# LinuxBoard_v1_91.net
KiCad netlist of a schematic drawn in EAGLE
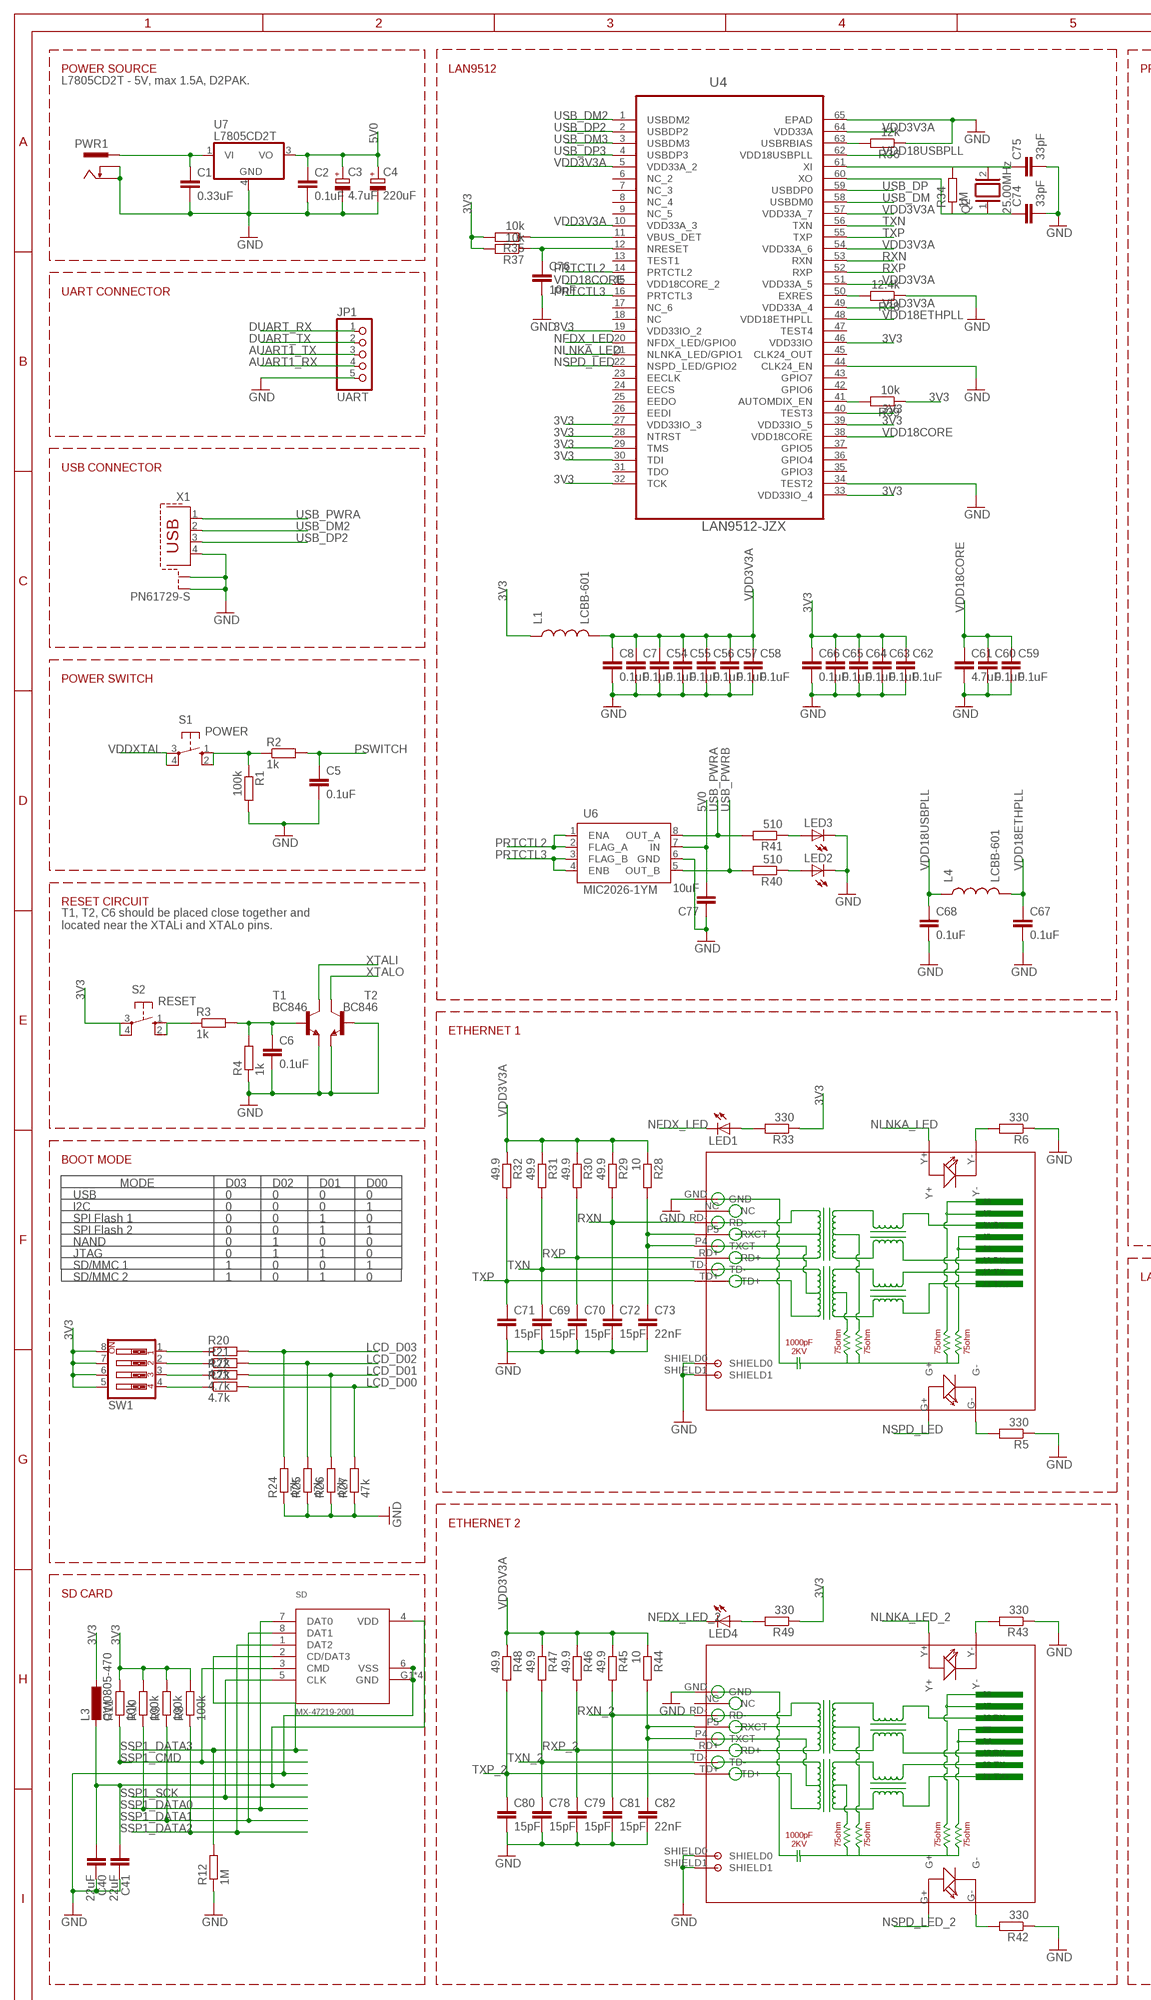
[diagram p0: schematic, sheet 1, part 1 of 2]
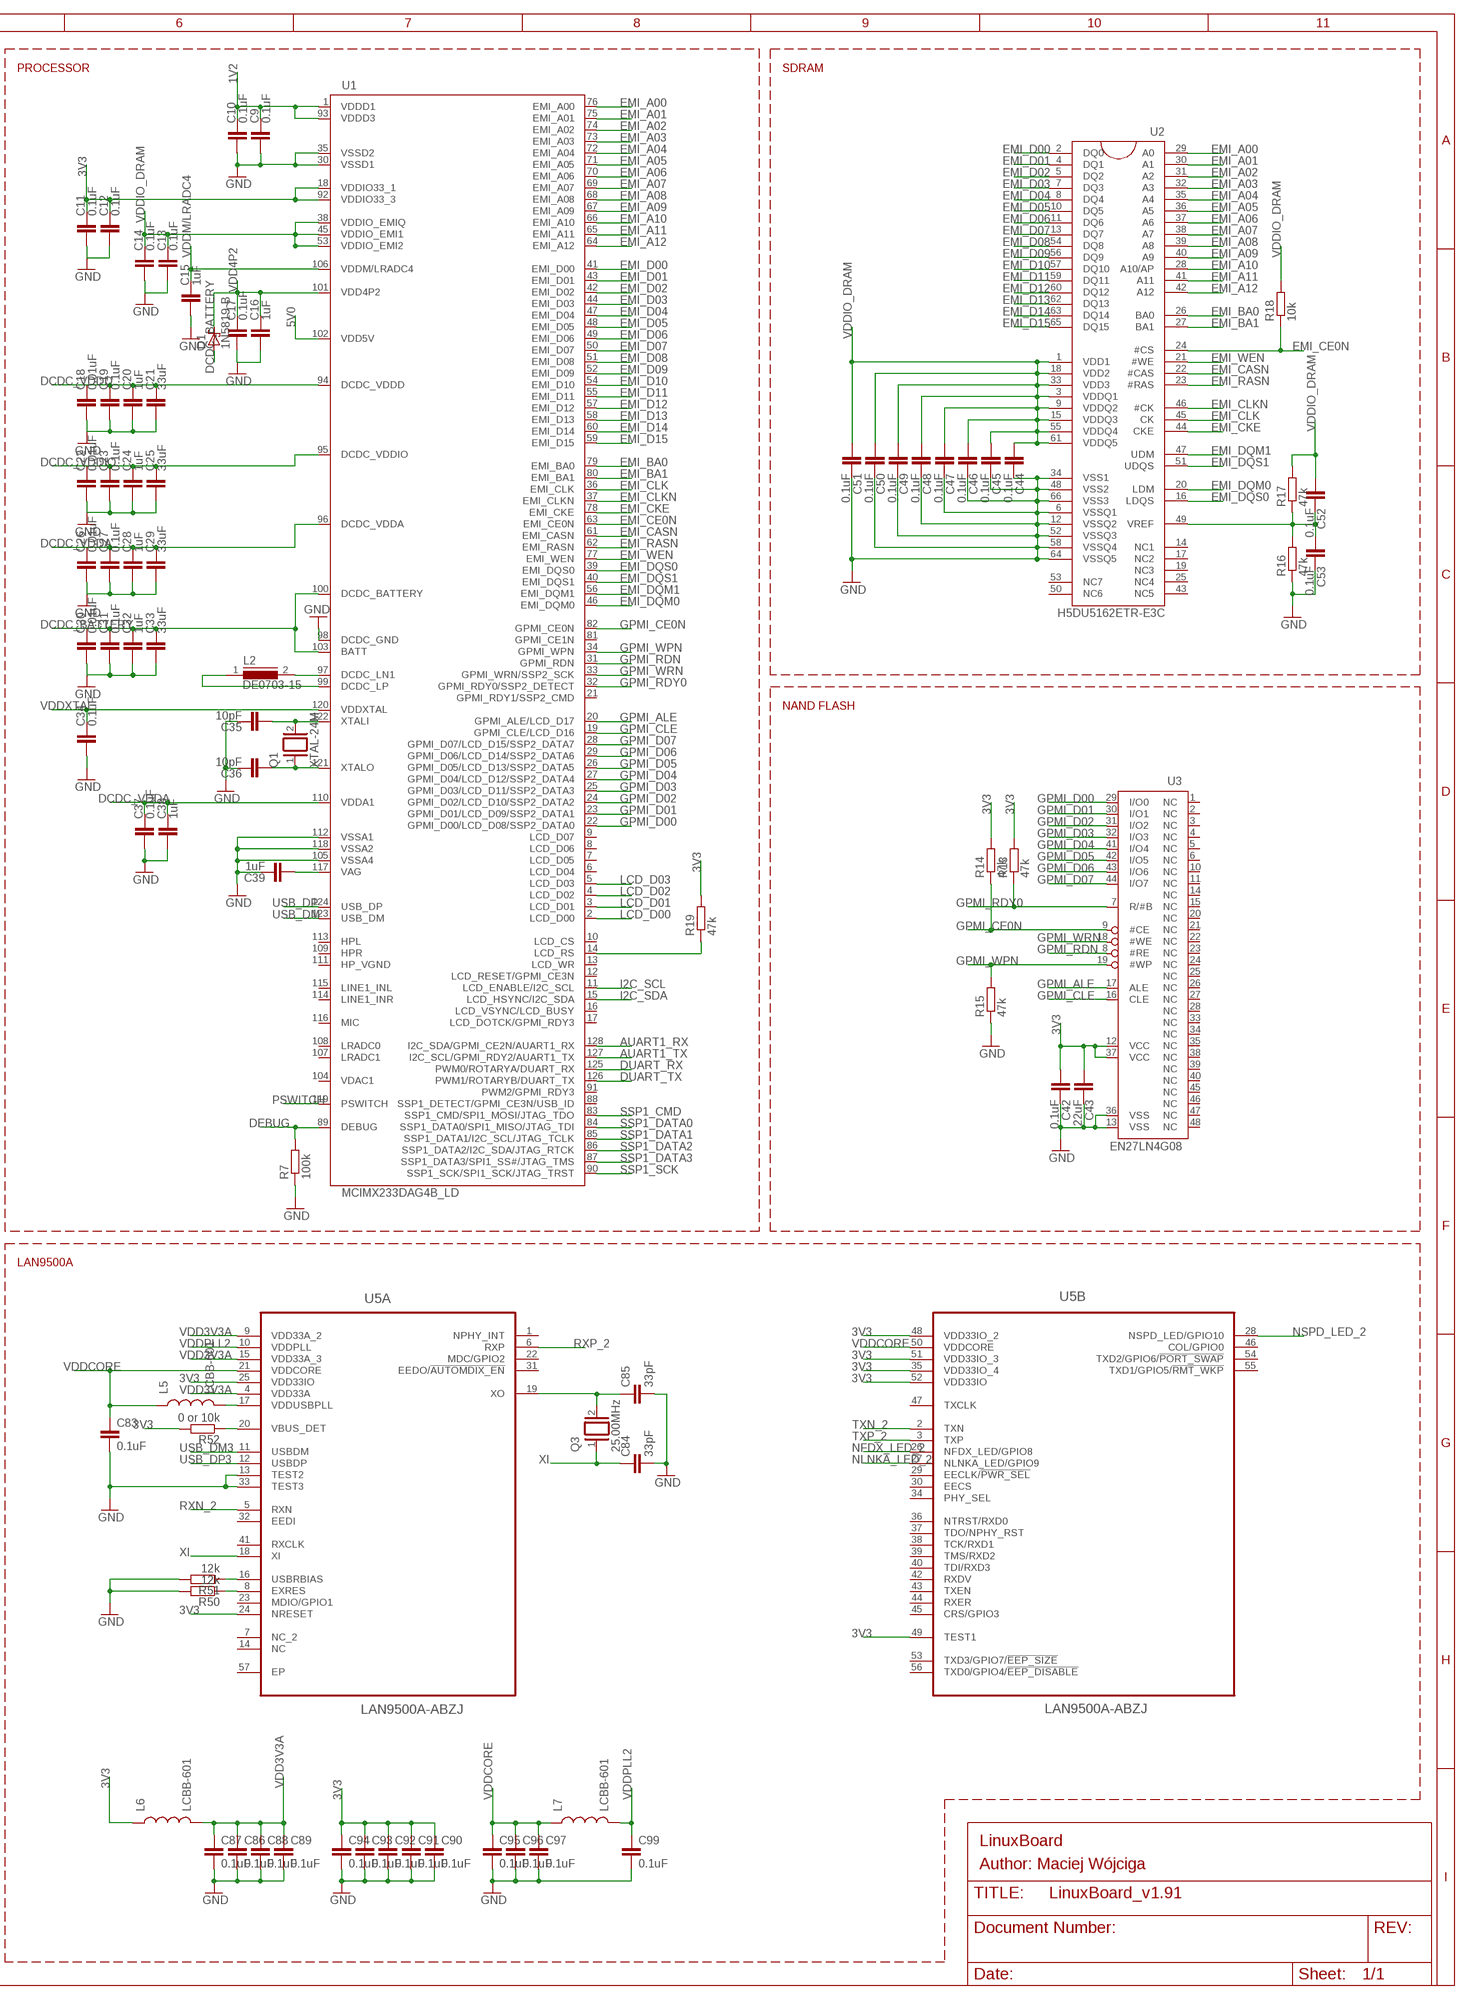
[diagram p1: schematic, sheet 1, part 2 of 2]

(export (version "E")
  (design (tool "Eeschema 10.0.6"))
  (components
    (comp (ref "C1")
      (value "0.33uF")
      (footprint "eagle-import:C0805")
      (libsource (lib "eagle-import") (part "C-EUC0805"))
    )
    (comp (ref "C2")
      (value "0.1uF")
      (footprint "eagle-import:C0805")
      (libsource (lib "eagle-import") (part "C-EUC0805"))
    )
    (comp (ref "C3")
      (value "4.7uF")
      (footprint "eagle-import:E2-5")
      (libsource (lib "eagle-import") (part "CPOL-EUE2-5"))
    )
    (comp (ref "C4")
      (value "220uF")
      (footprint "eagle-import:E2-5")
      (libsource (lib "eagle-import") (part "CPOL-EUE2-5"))
    )
    (comp (ref "C5")
      (value "0.1uF")
      (footprint "eagle-import:C0805")
      (libsource (lib "eagle-import") (part "C-EUC0805"))
    )
    (comp (ref "C6")
      (value "0.1uF")
      (footprint "eagle-import:C0805")
      (libsource (lib "eagle-import") (part "C-EUC0805"))
    )
    (comp (ref "C7")
      (value "0.1uF")
      (footprint "eagle-import:C0805")
      (libsource (lib "eagle-import") (part "C-EUC0805"))
    )
    (comp (ref "C8")
      (value "0.1uF")
      (footprint "eagle-import:C0805")
      (libsource (lib "eagle-import") (part "C-EUC0805"))
    )
    (comp (ref "C9")
      (value "0.1uF")
      (footprint "eagle-import:C0805")
      (libsource (lib "eagle-import") (part "C-EUC0805"))
    )
    (comp (ref "C10")
      (value "0.1uF")
      (footprint "eagle-import:C0805")
      (libsource (lib "eagle-import") (part "C-EUC0805"))
    )
    (comp (ref "C11")
      (value "0.1uF")
      (footprint "eagle-import:C0805")
      (libsource (lib "eagle-import") (part "C-EUC0805"))
    )
    (comp (ref "C12")
      (value "0.1uF")
      (footprint "eagle-import:C0805")
      (libsource (lib "eagle-import") (part "C-EUC0805"))
    )
    (comp (ref "C13")
      (value "0.1uF")
      (footprint "eagle-import:C0805")
      (libsource (lib "eagle-import") (part "C-EUC0805"))
    )
    (comp (ref "C14")
      (value "0.1uF")
      (footprint "eagle-import:C0805")
      (libsource (lib "eagle-import") (part "C-EUC0805"))
    )
    (comp (ref "C15")
      (value "1uF")
      (footprint "eagle-import:C0805")
      (libsource (lib "eagle-import") (part "C-EUC0805"))
    )
    (comp (ref "C16")
      (value "1uF")
      (footprint "eagle-import:C0805")
      (libsource (lib "eagle-import") (part "C-EUC0805"))
    )
    (comp (ref "C17")
      (value "0.1uF")
      (footprint "eagle-import:C0805")
      (libsource (lib "eagle-import") (part "C-EUC0805"))
    )
    (comp (ref "C18")
      (value "0.01uF")
      (footprint "eagle-import:C0805")
      (libsource (lib "eagle-import") (part "C-EUC0805"))
    )
    (comp (ref "C19")
      (value "0.1uF")
      (footprint "eagle-import:C0805")
      (libsource (lib "eagle-import") (part "C-EUC0805"))
    )
    (comp (ref "C20")
      (value "1uF")
      (footprint "eagle-import:C0805")
      (libsource (lib "eagle-import") (part "C-EUC0805"))
    )
    (comp (ref "C21")
      (value "33uF")
      (footprint "eagle-import:C0805")
      (libsource (lib "eagle-import") (part "C-EUC0805"))
    )
    (comp (ref "C22")
      (value "0.01uF")
      (footprint "eagle-import:C0805")
      (libsource (lib "eagle-import") (part "C-EUC0805"))
    )
    (comp (ref "C23")
      (value "0.1uF")
      (footprint "eagle-import:C0805")
      (libsource (lib "eagle-import") (part "C-EUC0805"))
    )
    (comp (ref "C24")
      (value "1uF")
      (footprint "eagle-import:C0805")
      (libsource (lib "eagle-import") (part "C-EUC0805"))
    )
    (comp (ref "C25")
      (value "33uF")
      (footprint "eagle-import:C0805")
      (libsource (lib "eagle-import") (part "C-EUC0805"))
    )
    (comp (ref "C26")
      (value "0.01uF")
      (footprint "eagle-import:C0805")
      (libsource (lib "eagle-import") (part "C-EUC0805"))
    )
    (comp (ref "C27")
      (value "0.1uF")
      (footprint "eagle-import:C0805")
      (libsource (lib "eagle-import") (part "C-EUC0805"))
    )
    (comp (ref "C28")
      (value "1uF")
      (footprint "eagle-import:C0805")
      (libsource (lib "eagle-import") (part "C-EUC0805"))
    )
    (comp (ref "C29")
      (value "33uF")
      (footprint "eagle-import:C0805")
      (libsource (lib "eagle-import") (part "C-EUC0805"))
    )
    (comp (ref "C30")
      (value "0.01uF")
      (footprint "eagle-import:C0805")
      (libsource (lib "eagle-import") (part "C-EUC0805"))
    )
    (comp (ref "C31")
      (value "0.1uF")
      (footprint "eagle-import:C0805")
      (libsource (lib "eagle-import") (part "C-EUC0805"))
    )
    (comp (ref "C32")
      (value "1uF")
      (footprint "eagle-import:C0805")
      (libsource (lib "eagle-import") (part "C-EUC0805"))
    )
    (comp (ref "C33")
      (value "33uF")
      (footprint "eagle-import:C0805")
      (libsource (lib "eagle-import") (part "C-EUC0805"))
    )
    (comp (ref "C34")
      (value "0.1uF")
      (footprint "eagle-import:C0805")
      (libsource (lib "eagle-import") (part "C-EUC0805"))
    )
    (comp (ref "C35")
      (value "10pF")
      (footprint "eagle-import:C0805")
      (libsource (lib "eagle-import") (part "C-EUC0805"))
    )
    (comp (ref "C36")
      (value "10pF")
      (footprint "eagle-import:C0805")
      (libsource (lib "eagle-import") (part "C-EUC0805"))
    )
    (comp (ref "C37")
      (value "0.1uF")
      (footprint "eagle-import:C0805")
      (libsource (lib "eagle-import") (part "C-EUC0805"))
    )
    (comp (ref "C38")
      (value "1uF")
      (footprint "eagle-import:C0805")
      (libsource (lib "eagle-import") (part "C-EUC0805"))
    )
    (comp (ref "C39")
      (value "1uF")
      (footprint "eagle-import:C0805")
      (libsource (lib "eagle-import") (part "C-EUC0805"))
    )
    (comp (ref "C40")
      (value "22uF")
      (footprint "eagle-import:C0805")
      (libsource (lib "eagle-import") (part "C-EUC0805"))
    )
    (comp (ref "C41")
      (value "22uF")
      (footprint "eagle-import:C0805")
      (libsource (lib "eagle-import") (part "C-EUC0805"))
    )
    (comp (ref "C42")
      (value "0.1uF")
      (footprint "eagle-import:C0805")
      (libsource (lib "eagle-import") (part "C-EUC0805"))
    )
    (comp (ref "C43")
      (value "22uF")
      (footprint "eagle-import:C0805")
      (libsource (lib "eagle-import") (part "C-EUC0805"))
    )
    (comp (ref "C44")
      (value "0.1uF")
      (footprint "eagle-import:C0805")
      (libsource (lib "eagle-import") (part "C-EUC0805"))
    )
    (comp (ref "C45")
      (value "0.1uF")
      (footprint "eagle-import:C0805")
      (libsource (lib "eagle-import") (part "C-EUC0805"))
    )
    (comp (ref "C46")
      (value "0.1uF")
      (footprint "eagle-import:C0805")
      (libsource (lib "eagle-import") (part "C-EUC0805"))
    )
    (comp (ref "C47")
      (value "0.1uF")
      (footprint "eagle-import:C0805")
      (libsource (lib "eagle-import") (part "C-EUC0805"))
    )
    (comp (ref "C48")
      (value "0.1uF")
      (footprint "eagle-import:C0805")
      (libsource (lib "eagle-import") (part "C-EUC0805"))
    )
    (comp (ref "C49")
      (value "0.1uF")
      (footprint "eagle-import:C0805")
      (libsource (lib "eagle-import") (part "C-EUC0805"))
    )
    (comp (ref "C50")
      (value "0.1uF")
      (footprint "eagle-import:C0805")
      (libsource (lib "eagle-import") (part "C-EUC0805"))
    )
    (comp (ref "C51")
      (value "0.1uF")
      (footprint "eagle-import:C0805")
      (libsource (lib "eagle-import") (part "C-EUC0805"))
    )
    (comp (ref "C52")
      (value "0.1uF")
      (footprint "eagle-import:C0805")
      (libsource (lib "eagle-import") (part "C-EUC0805"))
    )
    (comp (ref "C53")
      (value "0.1uF")
      (footprint "eagle-import:C0805")
      (libsource (lib "eagle-import") (part "C-EUC0805"))
    )
    (comp (ref "C54")
      (value "0.1uF")
      (footprint "eagle-import:C0805")
      (libsource (lib "eagle-import") (part "C-EUC0805"))
    )
    (comp (ref "C55")
      (value "0.1uF")
      (footprint "eagle-import:C0805")
      (libsource (lib "eagle-import") (part "C-EUC0805"))
    )
    (comp (ref "C56")
      (value "0.1uF")
      (footprint "eagle-import:C0805")
      (libsource (lib "eagle-import") (part "C-EUC0805"))
    )
    (comp (ref "C57")
      (value "0.1uF")
      (footprint "eagle-import:C0805")
      (libsource (lib "eagle-import") (part "C-EUC0805"))
    )
    (comp (ref "C58")
      (value "0.1uF")
      (footprint "eagle-import:C0805")
      (libsource (lib "eagle-import") (part "C-EUC0805"))
    )
    (comp (ref "C59")
      (value "0.1uF")
      (footprint "eagle-import:C0805")
      (libsource (lib "eagle-import") (part "C-EUC0805"))
    )
    (comp (ref "C60")
      (value "0.1uF")
      (footprint "eagle-import:C0805")
      (libsource (lib "eagle-import") (part "C-EUC0805"))
    )
    (comp (ref "C61")
      (value "4.7uF")
      (footprint "eagle-import:C0805")
      (libsource (lib "eagle-import") (part "C-EUC0805"))
    )
    (comp (ref "C62")
      (value "0.1uF")
      (footprint "eagle-import:C0805")
      (libsource (lib "eagle-import") (part "C-EUC0805"))
    )
    (comp (ref "C63")
      (value "0.1uF")
      (footprint "eagle-import:C0805")
      (libsource (lib "eagle-import") (part "C-EUC0805"))
    )
    (comp (ref "C64")
      (value "0.1uF")
      (footprint "eagle-import:C0805")
      (libsource (lib "eagle-import") (part "C-EUC0805"))
    )
    (comp (ref "C65")
      (value "0.1uF")
      (footprint "eagle-import:C0805")
      (libsource (lib "eagle-import") (part "C-EUC0805"))
    )
    (comp (ref "C66")
      (value "0.1uF")
      (footprint "eagle-import:C0805")
      (libsource (lib "eagle-import") (part "C-EUC0805"))
    )
    (comp (ref "C67")
      (value "0.1uF")
      (footprint "eagle-import:C0805")
      (libsource (lib "eagle-import") (part "C-EUC0805"))
    )
    (comp (ref "C68")
      (value "0.1uF")
      (footprint "eagle-import:C0805")
      (libsource (lib "eagle-import") (part "C-EUC0805"))
    )
    (comp (ref "C69")
      (value "15pF")
      (footprint "eagle-import:C0805")
      (libsource (lib "eagle-import") (part "C-EUC0805"))
    )
    (comp (ref "C70")
      (value "15pF")
      (footprint "eagle-import:C0805")
      (libsource (lib "eagle-import") (part "C-EUC0805"))
    )
    (comp (ref "C71")
      (value "15pF")
      (footprint "eagle-import:C0805")
      (libsource (lib "eagle-import") (part "C-EUC0805"))
    )
    (comp (ref "C72")
      (value "15pF")
      (footprint "eagle-import:C0805")
      (libsource (lib "eagle-import") (part "C-EUC0805"))
    )
    (comp (ref "C73")
      (value "22nF")
      (footprint "eagle-import:C0805")
      (libsource (lib "eagle-import") (part "C-EUC0805"))
    )
    (comp (ref "C74")
      (value "33pF")
      (footprint "eagle-import:C0805")
      (libsource (lib "eagle-import") (part "C-EUC0805"))
    )
    (comp (ref "C75")
      (value "33pF")
      (footprint "eagle-import:C0805")
      (libsource (lib "eagle-import") (part "C-EUC0805"))
    )
    (comp (ref "C76")
      (value "10nF")
      (footprint "eagle-import:C0805")
      (libsource (lib "eagle-import") (part "C-EUC0805"))
    )
    (comp (ref "C77")
      (value "10uF")
      (footprint "eagle-import:C0805")
      (libsource (lib "eagle-import") (part "C-EUC0805"))
    )
    (comp (ref "C78")
      (value "15pF")
      (footprint "eagle-import:C0805")
      (libsource (lib "eagle-import") (part "C-EUC0805"))
    )
    (comp (ref "C79")
      (value "15pF")
      (footprint "eagle-import:C0805")
      (libsource (lib "eagle-import") (part "C-EUC0805"))
    )
    (comp (ref "C80")
      (value "15pF")
      (footprint "eagle-import:C0805")
      (libsource (lib "eagle-import") (part "C-EUC0805"))
    )
    (comp (ref "C81")
      (value "15pF")
      (footprint "eagle-import:C0805")
      (libsource (lib "eagle-import") (part "C-EUC0805"))
    )
    (comp (ref "C82")
      (value "22nF")
      (footprint "eagle-import:C0805")
      (libsource (lib "eagle-import") (part "C-EUC0805"))
    )
    (comp (ref "C83")
      (value "0.1uF")
      (footprint "eagle-import:C0805")
      (libsource (lib "eagle-import") (part "C-EUC0805"))
    )
    (comp (ref "C84")
      (value "33pF")
      (footprint "eagle-import:C0805")
      (libsource (lib "eagle-import") (part "C-EUC0805"))
    )
    (comp (ref "C85")
      (value "33pF")
      (footprint "eagle-import:C0805")
      (libsource (lib "eagle-import") (part "C-EUC0805"))
    )
    (comp (ref "C86")
      (value "0.1uF")
      (footprint "eagle-import:C0805")
      (libsource (lib "eagle-import") (part "C-EUC0805"))
    )
    (comp (ref "C87")
      (value "0.1uF")
      (footprint "eagle-import:C0805")
      (libsource (lib "eagle-import") (part "C-EUC0805"))
    )
    (comp (ref "C88")
      (value "0.1uF")
      (footprint "eagle-import:C0805")
      (libsource (lib "eagle-import") (part "C-EUC0805"))
    )
    (comp (ref "C89")
      (value "0.1uF")
      (footprint "eagle-import:C0805")
      (libsource (lib "eagle-import") (part "C-EUC0805"))
    )
    (comp (ref "C90")
      (value "0.1uF")
      (footprint "eagle-import:C0805")
      (libsource (lib "eagle-import") (part "C-EUC0805"))
    )
    (comp (ref "C91")
      (value "0.1uF")
      (footprint "eagle-import:C0805")
      (libsource (lib "eagle-import") (part "C-EUC0805"))
    )
    (comp (ref "C92")
      (value "0.1uF")
      (footprint "eagle-import:C0805")
      (libsource (lib "eagle-import") (part "C-EUC0805"))
    )
    (comp (ref "C93")
      (value "0.1uF")
      (footprint "eagle-import:C0805")
      (libsource (lib "eagle-import") (part "C-EUC0805"))
    )
    (comp (ref "C94")
      (value "0.1uF")
      (footprint "eagle-import:C0805")
      (libsource (lib "eagle-import") (part "C-EUC0805"))
    )
    (comp (ref "C95")
      (value "0.1uF")
      (footprint "eagle-import:C0805")
      (libsource (lib "eagle-import") (part "C-EUC0805"))
    )
    (comp (ref "C96")
      (value "0.1uF")
      (footprint "eagle-import:C0805")
      (libsource (lib "eagle-import") (part "C-EUC0805"))
    )
    (comp (ref "C97")
      (value "0.1uF")
      (footprint "eagle-import:C0805")
      (libsource (lib "eagle-import") (part "C-EUC0805"))
    )
    (comp (ref "C99")
      (value "0.1uF")
      (footprint "eagle-import:C0805")
      (libsource (lib "eagle-import") (part "C-EUC0805"))
    )
    (comp (ref "D1")
      (value "1N5819-B")
      (footprint "eagle-import:DO41-7.6")
      (libsource (lib "eagle-import") (part "1N5819-B"))
    )
    (comp (ref "JP1")
      (value "UART")
      (footprint "eagle-import:1X05")
      (libsource (lib "eagle-import") (part "PINHD-1X5"))
    )
    (comp (ref "L1")
      (value "LCBB-601")
      (footprint "eagle-import:0805")
      (libsource (lib "eagle-import") (part "INDUCTOR0805"))
    )
    (comp (ref "L2")
      (value "DE0703-15")
      (footprint "eagle-import:DR73")
      (libsource (lib "eagle-import") (part "DR73"))
    )
    (comp (ref "L3")
      (value "CW0805-470")
      (footprint "eagle-import:L2012C")
      (libsource (lib "eagle-import") (part "L-EUL2012C"))
    )
    (comp (ref "L4")
      (value "LCBB-601")
      (footprint "eagle-import:0805")
      (libsource (lib "eagle-import") (part "INDUCTOR0805"))
    )
    (comp (ref "L5")
      (value "LCBB-601")
      (footprint "eagle-import:0805")
      (libsource (lib "eagle-import") (part "INDUCTOR0805"))
    )
    (comp (ref "L6")
      (value "LCBB-601")
      (footprint "eagle-import:0805")
      (libsource (lib "eagle-import") (part "INDUCTOR0805"))
    )
    (comp (ref "L7")
      (value "LCBB-601")
      (footprint "eagle-import:0805")
      (libsource (lib "eagle-import") (part "INDUCTOR0805"))
    )
    (comp (ref "LED1")
      (value "LEDSML0805")
      (footprint "eagle-import:SML0805")
      (libsource (lib "eagle-import") (part "LEDSML0805"))
    )
    (comp (ref "LED2")
      (value "LEDSML0805")
      (footprint "eagle-import:SML0805")
      (libsource (lib "eagle-import") (part "LEDSML0805"))
    )
    (comp (ref "LED3")
      (value "LEDSML0805")
      (footprint "eagle-import:SML0805")
      (libsource (lib "eagle-import") (part "LEDSML0805"))
    )
    (comp (ref "LED4")
      (value "LEDSML0805")
      (footprint "eagle-import:SML0805")
      (libsource (lib "eagle-import") (part "LEDSML0805"))
    )
    (comp (ref "PWR1")
      (value "PWR-JAKPWR_JACK_UNI_MILLING")
      (footprint "eagle-import:PWR_JACK_UNI_MILLING")
      (libsource (lib "eagle-import") (part "PWR-JAKPWR_JACK_UNI_MILLING"))
    )
    (comp (ref "Q1")
      (value "XTAL-24M")
      (footprint "eagle-import:QS")
      (libsource (lib "eagle-import") (part "XTAL/S"))
    )
    (comp (ref "Q2")
      (value "25.00MHz")
      (footprint "eagle-import:QS")
      (libsource (lib "eagle-import") (part "XTAL/S"))
    )
    (comp (ref "Q3")
      (value "25.00MHz")
      (footprint "eagle-import:QS")
      (libsource (lib "eagle-import") (part "XTAL/S"))
    )
    (comp (ref "R1")
      (value "100k")
      (footprint "eagle-import:R0805")
      (libsource (lib "eagle-import") (part "R-EU_R0805"))
    )
    (comp (ref "R2")
      (value "1k")
      (footprint "eagle-import:R0805")
      (libsource (lib "eagle-import") (part "R-EU_R0805"))
    )
    (comp (ref "R3")
      (value "1k")
      (footprint "eagle-import:R0805")
      (libsource (lib "eagle-import") (part "R-EU_R0805"))
    )
    (comp (ref "R4")
      (value "1k")
      (footprint "eagle-import:R0805")
      (libsource (lib "eagle-import") (part "R-EU_R0805"))
    )
    (comp (ref "R5")
      (value "330")
      (footprint "eagle-import:R0805")
      (libsource (lib "eagle-import") (part "R-EU_R0805"))
    )
    (comp (ref "R6")
      (value "330")
      (footprint "eagle-import:R0805")
      (libsource (lib "eagle-import") (part "R-EU_R0805"))
    )
    (comp (ref "R7")
      (value "100k")
      (footprint "eagle-import:R0805")
      (libsource (lib "eagle-import") (part "R-EU_R0805"))
    )
    (comp (ref "R8")
      (value "100k")
      (footprint "eagle-import:R0805")
      (libsource (lib "eagle-import") (part "R-EU_R0805"))
    )
    (comp (ref "R9")
      (value "100k")
      (footprint "eagle-import:R0805")
      (libsource (lib "eagle-import") (part "R-EU_R0805"))
    )
    (comp (ref "R10")
      (value "100k")
      (footprint "eagle-import:R0805")
      (libsource (lib "eagle-import") (part "R-EU_R0805"))
    )
    (comp (ref "R11")
      (value "10k")
      (footprint "eagle-import:R0805")
      (libsource (lib "eagle-import") (part "R-EU_R0805"))
    )
    (comp (ref "R12")
      (value "1M")
      (footprint "eagle-import:R0805")
      (libsource (lib "eagle-import") (part "R-EU_R0805"))
    )
    (comp (ref "R13")
      (value "47k")
      (footprint "eagle-import:R0805")
      (libsource (lib "eagle-import") (part "R-EU_R0805"))
    )
    (comp (ref "R14")
      (value "47k")
      (footprint "eagle-import:R0805")
      (libsource (lib "eagle-import") (part "R-EU_R0805"))
    )
    (comp (ref "R15")
      (value "47k")
      (footprint "eagle-import:R0805")
      (libsource (lib "eagle-import") (part "R-EU_R0805"))
    )
    (comp (ref "R16")
      (value "47k")
      (footprint "eagle-import:R0805")
      (libsource (lib "eagle-import") (part "R-EU_R0805"))
    )
    (comp (ref "R17")
      (value "47k")
      (footprint "eagle-import:R0805")
      (libsource (lib "eagle-import") (part "R-EU_R0805"))
    )
    (comp (ref "R18")
      (value "10k")
      (footprint "eagle-import:R0805")
      (libsource (lib "eagle-import") (part "R-EU_R0805"))
    )
    (comp (ref "R19")
      (value "47k")
      (footprint "eagle-import:R0805")
      (libsource (lib "eagle-import") (part "R-EU_R0805"))
    )
    (comp (ref "R20")
      (value "4.7k")
      (footprint "eagle-import:R0805")
      (libsource (lib "eagle-import") (part "R-EU_R0805"))
    )
    (comp (ref "R21")
      (value "4.7k")
      (footprint "eagle-import:R0805")
      (libsource (lib "eagle-import") (part "R-EU_R0805"))
    )
    (comp (ref "R22")
      (value "4.7k")
      (footprint "eagle-import:R0805")
      (libsource (lib "eagle-import") (part "R-EU_R0805"))
    )
    (comp (ref "R23")
      (value "4.7k")
      (footprint "eagle-import:R0805")
      (libsource (lib "eagle-import") (part "R-EU_R0805"))
    )
    (comp (ref "R24")
      (value "47k")
      (footprint "eagle-import:R0805")
      (libsource (lib "eagle-import") (part "R-EU_R0805"))
    )
    (comp (ref "R25")
      (value "47k")
      (footprint "eagle-import:R0805")
      (libsource (lib "eagle-import") (part "R-EU_R0805"))
    )
    (comp (ref "R26")
      (value "47k")
      (footprint "eagle-import:R0805")
      (libsource (lib "eagle-import") (part "R-EU_R0805"))
    )
    (comp (ref "R27")
      (value "47k")
      (footprint "eagle-import:R0805")
      (libsource (lib "eagle-import") (part "R-EU_R0805"))
    )
    (comp (ref "R28")
      (value "10")
      (footprint "eagle-import:R0805")
      (libsource (lib "eagle-import") (part "R-EU_R0805"))
    )
    (comp (ref "R29")
      (value "49.9")
      (footprint "eagle-import:R0805")
      (libsource (lib "eagle-import") (part "R-EU_R0805"))
    )
    (comp (ref "R30")
      (value "49.9")
      (footprint "eagle-import:R0805")
      (libsource (lib "eagle-import") (part "R-EU_R0805"))
    )
    (comp (ref "R31")
      (value "49.9")
      (footprint "eagle-import:R0805")
      (libsource (lib "eagle-import") (part "R-EU_R0805"))
    )
    (comp (ref "R32")
      (value "49.9")
      (footprint "eagle-import:R0805")
      (libsource (lib "eagle-import") (part "R-EU_R0805"))
    )
    (comp (ref "R33")
      (value "330")
      (footprint "eagle-import:R0805")
      (libsource (lib "eagle-import") (part "R-EU_R0805"))
    )
    (comp (ref "R34")
      (value "1M")
      (footprint "eagle-import:R0805")
      (libsource (lib "eagle-import") (part "R-EU_R0805"))
    )
    (comp (ref "R35")
      (value "10k")
      (footprint "eagle-import:R0805")
      (libsource (lib "eagle-import") (part "R-EU_R0805"))
    )
    (comp (ref "R36")
      (value "12k")
      (footprint "eagle-import:R0805")
      (libsource (lib "eagle-import") (part "R-EU_R0805"))
    )
    (comp (ref "R37")
      (value "10k")
      (footprint "eagle-import:R0805")
      (libsource (lib "eagle-import") (part "R-EU_R0805"))
    )
    (comp (ref "R38")
      (value "12.4k")
      (footprint "eagle-import:R0805")
      (libsource (lib "eagle-import") (part "R-EU_R0805"))
    )
    (comp (ref "R39")
      (value "10k")
      (footprint "eagle-import:R0805")
      (libsource (lib "eagle-import") (part "R-EU_R0805"))
    )
    (comp (ref "R40")
      (value "510")
      (footprint "eagle-import:R0805")
      (libsource (lib "eagle-import") (part "R-EU_R0805"))
    )
    (comp (ref "R41")
      (value "510")
      (footprint "eagle-import:R0805")
      (libsource (lib "eagle-import") (part "R-EU_R0805"))
    )
    (comp (ref "R42")
      (value "330")
      (footprint "eagle-import:R0805")
      (libsource (lib "eagle-import") (part "R-EU_R0805"))
    )
    (comp (ref "R43")
      (value "330")
      (footprint "eagle-import:R0805")
      (libsource (lib "eagle-import") (part "R-EU_R0805"))
    )
    (comp (ref "R44")
      (value "10")
      (footprint "eagle-import:R0805")
      (libsource (lib "eagle-import") (part "R-EU_R0805"))
    )
    (comp (ref "R45")
      (value "49.9")
      (footprint "eagle-import:R0805")
      (libsource (lib "eagle-import") (part "R-EU_R0805"))
    )
    (comp (ref "R46")
      (value "49.9")
      (footprint "eagle-import:R0805")
      (libsource (lib "eagle-import") (part "R-EU_R0805"))
    )
    (comp (ref "R47")
      (value "49.9")
      (footprint "eagle-import:R0805")
      (libsource (lib "eagle-import") (part "R-EU_R0805"))
    )
    (comp (ref "R48")
      (value "49.9")
      (footprint "eagle-import:R0805")
      (libsource (lib "eagle-import") (part "R-EU_R0805"))
    )
    (comp (ref "R49")
      (value "330")
      (footprint "eagle-import:R0805")
      (libsource (lib "eagle-import") (part "R-EU_R0805"))
    )
    (comp (ref "R50")
      (value "12k")
      (footprint "eagle-import:R0805")
      (libsource (lib "eagle-import") (part "R-EU_R0805"))
    )
    (comp (ref "R51")
      (value "12k")
      (footprint "eagle-import:R0805")
      (libsource (lib "eagle-import") (part "R-EU_R0805"))
    )
    (comp (ref "R52")
      (value "0 or 10k")
      (footprint "eagle-import:R0805")
      (libsource (lib "eagle-import") (part "R-EU_R0805"))
    )
    (comp (ref "RJ1")
      (value "HR911105A")
      (footprint "eagle-import:HR911105A")
      (libsource (lib "eagle-import") (part "HR911105A"))
    )
    (comp (ref "RJ2")
      (value "HR911105A")
      (footprint "eagle-import:HR911105A")
      (libsource (lib "eagle-import") (part "HR911105A"))
    )
    (comp (ref "S1")
      (value "POWER")
      (footprint "eagle-import:B3F-10XX")
      (fields (field (name "MPN") "B3F-1000"))
      (libsource (lib "eagle-import") (part "10-XX"))
    )
    (comp (ref "S2")
      (value "RESET")
      (footprint "eagle-import:B3F-10XX")
      (fields (field (name "MPN") "B3F-1000"))
      (libsource (lib "eagle-import") (part "10-XX"))
    )
    (comp (ref "SD")
      (value "MX-47219-2001")
      (footprint "eagle-import:MX-47219-2001")
      (libsource (lib "eagle-import") (part "MX-47219-2001"))
    )
    (comp (ref "SW1")
      (value "SW_DIP-4")
      (footprint "eagle-import:EDG-04")
      (libsource (lib "eagle-import") (part "SW_DIP-4"))
    )
    (comp (ref "T1")
      (value "BC846")
      (footprint "eagle-import:SOT23")
      (libsource (lib "eagle-import") (part "BC846"))
    )
    (comp (ref "T2")
      (value "BC846")
      (footprint "eagle-import:SOT23")
      (libsource (lib "eagle-import") (part "BC846"))
    )
    (comp (ref "U1")
      (value "MCIMX233DAG4B_LD")
      (footprint "eagle-import:TQFP128LD")
      (libsource (lib "eagle-import") (part "MCIMX233DAG4B_LD"))
    )
    (comp (ref "U2")
      (value "H5DU5162ETR-E3C")
      (footprint "eagle-import:66TSOP-II")
      (libsource (lib "eagle-import") (part "HY5DU121622D(L)T(P)-J"))
    )
    (comp (ref "U3")
      (value "EN27LN4G08")
      (footprint "eagle-import:TSOP48")
      (libsource (lib "eagle-import") (part "H27UBG8T2A"))
    )
    (comp (ref "U4")
      (value "LAN9512-JZX")
      (footprint "eagle-import:QFN50P900X900X100-65N")
      (libsource (lib "eagle-import") (part "LAN9512-JZX"))
    )
    (comp (ref "U5")
      (value "LAN9500A-ABZJ")
      (footprint "eagle-import:QFN50P800X800X100-57N")
      (libsource (lib "eagle-import") (part "LAN9500A-ABZJ"))
    )
    (comp (ref "U6")
      (value "MIC2026-1YM")
      (footprint "eagle-import:SO-8")
      (libsource (lib "eagle-import") (part "MIC2026-1YM"))
    )
    (comp (ref "U7")
      (value "L7805CD2T")
      (footprint "eagle-import:D2PAK-3")
      (libsource (lib "eagle-import") (part "L7805CD2T"))
    )
    (comp (ref "X1")
      (value "PN61729-S")
      (footprint "eagle-import:PN61729-S")
      (libsource (lib "eagle-import") (part "PN61729-S"))
    )
  )
  (nets
    (net (code "1") (name "/1V2") (class "Default")
      (node (ref "C10") (pin "1") (pinfunction "1_1") (pintype "passive"))
      (node (ref "C9") (pin "1") (pinfunction "1_1") (pintype "passive"))
      (node (ref "U1") (pin "1") (pinfunction "VDDD1_1") (pintype "power_in"))
      (node (ref "U1") (pin "93") (pinfunction "VDDD3_93") (pintype "power_in"))
    )
    (net (code "2") (name "/3V3") (class "Default")
      (node (ref "C11") (pin "1") (pinfunction "1_1") (pintype "passive"))
      (node (ref "C12") (pin "1") (pinfunction "1_1") (pintype "passive"))
      (node (ref "C42") (pin "2") (pinfunction "2_2") (pintype "passive"))
      (node (ref "C43") (pin "2") (pinfunction "2_2") (pintype "passive"))
      (node (ref "C62") (pin "1") (pinfunction "1_1") (pintype "passive"))
      (node (ref "C63") (pin "1") (pinfunction "1_1") (pintype "passive"))
      (node (ref "C64") (pin "1") (pinfunction "1_1") (pintype "passive"))
      (node (ref "C65") (pin "1") (pinfunction "1_1") (pintype "passive"))
      (node (ref "C66") (pin "1") (pinfunction "1_1") (pintype "passive"))
      (node (ref "C90") (pin "1") (pinfunction "1_1") (pintype "passive"))
      (node (ref "C91") (pin "1") (pinfunction "1_1") (pintype "passive"))
      (node (ref "C92") (pin "1") (pinfunction "1_1") (pintype "passive"))
      (node (ref "C93") (pin "1") (pinfunction "1_1") (pintype "passive"))
      (node (ref "C94") (pin "1") (pinfunction "1_1") (pintype "passive"))
      (node (ref "L1") (pin "1") (pinfunction "1_1") (pintype "passive"))
      (node (ref "L3") (pin "1") (pinfunction "1_1") (pintype "passive"))
      (node (ref "L6") (pin "1") (pinfunction "1_1") (pintype "passive"))
      (node (ref "R10") (pin "2") (pinfunction "2_2") (pintype "passive"))
      (node (ref "R11") (pin "2") (pinfunction "2_2") (pintype "passive"))
      (node (ref "R13") (pin "2") (pinfunction "2_2") (pintype "passive"))
      (node (ref "R14") (pin "2") (pinfunction "2_2") (pintype "passive"))
      (node (ref "R19") (pin "2") (pinfunction "2_2") (pintype "passive"))
      (node (ref "R33") (pin "1") (pinfunction "1_1") (pintype "passive"))
      (node (ref "R35") (pin "2") (pinfunction "2_2") (pintype "passive"))
      (node (ref "R37") (pin "2") (pinfunction "2_2") (pintype "passive"))
      (node (ref "R39") (pin "1") (pinfunction "1_1") (pintype "passive"))
      (node (ref "R49") (pin "1") (pinfunction "1_1") (pintype "passive"))
      (node (ref "R52") (pin "2") (pinfunction "2_2") (pintype "passive"))
      (node (ref "R8") (pin "2") (pinfunction "2_2") (pintype "passive"))
      (node (ref "R9") (pin "2") (pinfunction "2_2") (pintype "passive"))
      (node (ref "S2") (pin "3") (pinfunction "P_3") (pintype "passive"))
      (node (ref "S2") (pin "4") (pinfunction "P1_4") (pintype "passive"))
      (node (ref "SW1") (pin "5") (pinfunction "5_5") (pintype "passive"))
      (node (ref "SW1") (pin "6") (pinfunction "6_6") (pintype "passive"))
      (node (ref "SW1") (pin "7") (pinfunction "7_7") (pintype "passive"))
      (node (ref "SW1") (pin "8") (pinfunction "8_8") (pintype "passive"))
      (node (ref "U1") (pin "18") (pinfunction "VDDIO33_1_18") (pintype "power_in"))
      (node (ref "U1") (pin "92") (pinfunction "VDDIO33_3_92") (pintype "power_in"))
      (node (ref "U3") (pin "12") (pinfunction "VCC_12") (pintype "power_in"))
      (node (ref "U3") (pin "37") (pinfunction "VCC_37") (pintype "power_in"))
      (node (ref "U4") (pin "19") (pinfunction "VDD33IO_2_19") (pintype "power_in"))
      (node (ref "U4") (pin "27") (pinfunction "VDD33IO_3_27") (pintype "power_in"))
      (node (ref "U4") (pin "28") (pinfunction "NTRST_28") (pintype "passive"))
      (node (ref "U4") (pin "29") (pinfunction "TMS_29") (pintype "passive"))
      (node (ref "U4") (pin "30") (pinfunction "TDI_30") (pintype "passive"))
      (node (ref "U4") (pin "32") (pinfunction "TCK_32") (pintype "passive"))
      (node (ref "U4") (pin "33") (pinfunction "VDD33IO_4_33") (pintype "power_in"))
      (node (ref "U4") (pin "39") (pinfunction "VDD33IO_5_39") (pintype "power_in"))
      (node (ref "U4") (pin "40") (pinfunction "TEST3_40") (pintype "passive"))
      (node (ref "U4") (pin "46") (pinfunction "VDD33IO_46") (pintype "power_in"))
      (node (ref "U5") (pin "24") (pinfunction "NRESET_24") (pintype "input"))
      (node (ref "U5") (pin "25") (pinfunction "VDD33IO_25") (pintype "power_in"))
      (node (ref "U5") (pin "35") (pinfunction "VDD33IO_4_35") (pintype "power_in"))
      (node (ref "U5") (pin "48") (pinfunction "VDD33IO_2_48") (pintype "power_in"))
      (node (ref "U5") (pin "49") (pinfunction "TEST1_49") (pintype "power_in"))
      (node (ref "U5") (pin "51") (pinfunction "VDD33IO_3_51") (pintype "power_in"))
      (node (ref "U5") (pin "52") (pinfunction "VDD33IO_52") (pintype "power_in"))
    )
    (net (code "3") (name "/5V0") (class "Default")
      (node (ref "C2") (pin "1") (pinfunction "1_1") (pintype "passive"))
      (node (ref "C3") (pin "+") (pinfunction "+_+") (pintype "passive"))
      (node (ref "C4") (pin "+") (pinfunction "+_+") (pintype "passive"))
      (node (ref "C77") (pin "2") (pinfunction "2_2") (pintype "passive"))
      (node (ref "U1") (pin "102") (pinfunction "VDD5V_102") (pintype "power_in"))
      (node (ref "U6") (pin "7") (pinfunction "IN_7") (pintype "input"))
      (node (ref "U7") (pin "3") (pinfunction "VO_3") (pintype "passive"))
    )
    (net (code "4") (name "/AUART1_RX") (class "Default")
      (node (ref "JP1") (pin "4") (pinfunction "4_4") (pintype "passive"))
      (node (ref "U1") (pin "128") (pinfunction "I2C_SDA/GPMI_CE2N/AUART1_RX_128") (pintype "bidirectional"))
    )
    (net (code "5") (name "/AUART1_TX") (class "Default")
      (node (ref "JP1") (pin "3") (pinfunction "3_3") (pintype "passive"))
      (node (ref "U1") (pin "127") (pinfunction "I2C_SCL/GPMI_RDY2/AUART1_TX_127") (pintype "bidirectional"))
    )
    (net (code "6") (name "/DCDC_BATTERY") (class "Default")
      (node (ref "C30") (pin "1") (pinfunction "1_1") (pintype "passive"))
      (node (ref "C31") (pin "1") (pinfunction "1_1") (pintype "passive"))
      (node (ref "C32") (pin "1") (pinfunction "1_1") (pintype "passive"))
      (node (ref "C33") (pin "1") (pinfunction "1_1") (pintype "passive"))
      (node (ref "D1") (pin "A") (pinfunction "A_A") (pintype "passive"))
      (node (ref "U1") (pin "100") (pinfunction "DCDC_BATTERY_100") (pintype "power_in"))
      (node (ref "U1") (pin "103") (pinfunction "BATT_103") (pintype "input"))
    )
    (net (code "7") (name "/DCDC_VDDA") (class "Default")
      (node (ref "C26") (pin "1") (pinfunction "1_1") (pintype "passive"))
      (node (ref "C27") (pin "1") (pinfunction "1_1") (pintype "passive"))
      (node (ref "C28") (pin "1") (pinfunction "1_1") (pintype "passive"))
      (node (ref "C29") (pin "1") (pinfunction "1_1") (pintype "passive"))
      (node (ref "C37") (pin "1") (pinfunction "1_1") (pintype "passive"))
      (node (ref "C38") (pin "1") (pinfunction "1_1") (pintype "passive"))
      (node (ref "U1") (pin "110") (pinfunction "VDDA1_110") (pintype "power_in"))
      (node (ref "U1") (pin "96") (pinfunction "DCDC_VDDA_96") (pintype "power_in"))
    )
    (net (code "8") (name "/DCDC_VDDD") (class "Default")
      (node (ref "C18") (pin "1") (pinfunction "1_1") (pintype "passive"))
      (node (ref "C19") (pin "1") (pinfunction "1_1") (pintype "passive"))
      (node (ref "C20") (pin "1") (pinfunction "1_1") (pintype "passive"))
      (node (ref "C21") (pin "1") (pinfunction "1_1") (pintype "passive"))
      (node (ref "U1") (pin "94") (pinfunction "DCDC_VDDD_94") (pintype "power_in"))
    )
    (net (code "9") (name "/DCDC_VDDIO") (class "Default")
      (node (ref "C22") (pin "1") (pinfunction "1_1") (pintype "passive"))
      (node (ref "C23") (pin "1") (pinfunction "1_1") (pintype "passive"))
      (node (ref "C24") (pin "1") (pinfunction "1_1") (pintype "passive"))
      (node (ref "C25") (pin "1") (pinfunction "1_1") (pintype "passive"))
      (node (ref "U1") (pin "95") (pinfunction "DCDC_VDDIO_95") (pintype "power_in"))
    )
    (net (code "10") (name "/DEBUG") (class "Default")
      (node (ref "R7") (pin "2") (pinfunction "2_2") (pintype "passive"))
      (node (ref "U1") (pin "89") (pinfunction "DEBUG_89") (pintype "bidirectional"))
    )
    (net (code "11") (name "/DUART_RX") (class "Default")
      (node (ref "JP1") (pin "1") (pinfunction "1_1") (pintype "passive"))
      (node (ref "U1") (pin "125") (pinfunction "PWM0/ROTARYA/DUART_RX_125") (pintype "bidirectional"))
    )
    (net (code "12") (name "/DUART_TX") (class "Default")
      (node (ref "JP1") (pin "2") (pinfunction "2_2") (pintype "passive"))
      (node (ref "U1") (pin "126") (pinfunction "PWM1/ROTARYB/DUART_TX_126") (pintype "bidirectional"))
    )
    (net (code "13") (name "/EMI_A00") (class "Default")
      (node (ref "U1") (pin "76") (pinfunction "EMI_A00_76") (pintype "bidirectional"))
      (node (ref "U2") (pin "29") (pinfunction "A0_29") (pintype "input"))
    )
    (net (code "14") (name "/EMI_A01") (class "Default")
      (node (ref "U1") (pin "75") (pinfunction "EMI_A01_75") (pintype "bidirectional"))
      (node (ref "U2") (pin "30") (pinfunction "A1_30") (pintype "input"))
    )
    (net (code "15") (name "/EMI_A02") (class "Default")
      (node (ref "U1") (pin "74") (pinfunction "EMI_A02_74") (pintype "bidirectional"))
      (node (ref "U2") (pin "31") (pinfunction "A2_31") (pintype "input"))
    )
    (net (code "16") (name "/EMI_A03") (class "Default")
      (node (ref "U1") (pin "73") (pinfunction "EMI_A03_73") (pintype "bidirectional"))
      (node (ref "U2") (pin "32") (pinfunction "A3_32") (pintype "input"))
    )
    (net (code "17") (name "/EMI_A04") (class "Default")
      (node (ref "U1") (pin "72") (pinfunction "EMI_A04_72") (pintype "bidirectional"))
      (node (ref "U2") (pin "35") (pinfunction "A4_35") (pintype "input"))
    )
    (net (code "18") (name "/EMI_A05") (class "Default")
      (node (ref "U1") (pin "71") (pinfunction "EMI_A05_71") (pintype "bidirectional"))
      (node (ref "U2") (pin "36") (pinfunction "A5_36") (pintype "input"))
    )
    (net (code "19") (name "/EMI_A06") (class "Default")
      (node (ref "U1") (pin "70") (pinfunction "EMI_A06_70") (pintype "bidirectional"))
      (node (ref "U2") (pin "37") (pinfunction "A6_37") (pintype "input"))
    )
    (net (code "20") (name "/EMI_A07") (class "Default")
      (node (ref "U1") (pin "69") (pinfunction "EMI_A07_69") (pintype "bidirectional"))
      (node (ref "U2") (pin "38") (pinfunction "A7_38") (pintype "input"))
    )
    (net (code "21") (name "/EMI_A08") (class "Default")
      (node (ref "U1") (pin "68") (pinfunction "EMI_A08_68") (pintype "bidirectional"))
      (node (ref "U2") (pin "39") (pinfunction "A8_39") (pintype "input"))
    )
    (net (code "22") (name "/EMI_A09") (class "Default")
      (node (ref "U1") (pin "67") (pinfunction "EMI_A09_67") (pintype "bidirectional"))
      (node (ref "U2") (pin "40") (pinfunction "A9_40") (pintype "input"))
    )
    (net (code "23") (name "/EMI_A10") (class "Default")
      (node (ref "U1") (pin "66") (pinfunction "EMI_A10_66") (pintype "bidirectional"))
      (node (ref "U2") (pin "28") (pinfunction "A10/AP_28") (pintype "input"))
    )
    (net (code "24") (name "/EMI_A11") (class "Default")
      (node (ref "U1") (pin "65") (pinfunction "EMI_A11_65") (pintype "bidirectional"))
      (node (ref "U2") (pin "41") (pinfunction "A11_41") (pintype "input"))
    )
    (net (code "25") (name "/EMI_A12") (class "Default")
      (node (ref "U1") (pin "64") (pinfunction "EMI_A12_64") (pintype "bidirectional"))
      (node (ref "U2") (pin "42") (pinfunction "A12_42") (pintype "input"))
    )
    (net (code "26") (name "/EMI_BA0") (class "Default")
      (node (ref "U1") (pin "79") (pinfunction "EMI_BA0_79") (pintype "output"))
      (node (ref "U2") (pin "26") (pinfunction "BA0_26") (pintype "input"))
    )
    (net (code "27") (name "/EMI_BA1") (class "Default")
      (node (ref "U1") (pin "80") (pinfunction "EMI_BA1_80") (pintype "output"))
      (node (ref "U2") (pin "27") (pinfunction "BA1_27") (pintype "input"))
    )
    (net (code "28") (name "/EMI_CASN") (class "Default")
      (node (ref "U1") (pin "61") (pinfunction "EMI_CASN_61") (pintype "output"))
      (node (ref "U2") (pin "22") (pinfunction "#CAS_22") (pintype "input"))
    )
    (net (code "29") (name "/EMI_CE0N") (class "Default")
      (node (ref "R18") (pin "1") (pinfunction "1_1") (pintype "passive"))
      (node (ref "U1") (pin "63") (pinfunction "EMI_CE0N_63") (pintype "output"))
      (node (ref "U2") (pin "24") (pinfunction "#CS_24") (pintype "input"))
    )
    (net (code "30") (name "/EMI_CKE") (class "Default")
      (node (ref "U1") (pin "78") (pinfunction "EMI_CKE_78") (pintype "output"))
      (node (ref "U2") (pin "44") (pinfunction "CKE_44") (pintype "input"))
    )
    (net (code "31") (name "/EMI_CLK") (class "Default")
      (node (ref "U1") (pin "36") (pinfunction "EMI_CLK_36") (pintype "output"))
      (node (ref "U2") (pin "45") (pinfunction "CK_45") (pintype "input"))
    )
    (net (code "32") (name "/EMI_CLKN") (class "Default")
      (node (ref "U1") (pin "37") (pinfunction "EMI_CLKN_37") (pintype "output"))
      (node (ref "U2") (pin "46") (pinfunction "#CK_46") (pintype "input"))
    )
    (net (code "33") (name "/EMI_D00") (class "Default")
      (node (ref "U1") (pin "41") (pinfunction "EMI_D00_41") (pintype "bidirectional"))
      (node (ref "U2") (pin "2") (pinfunction "DQ0_2") (pintype "bidirectional"))
    )
    (net (code "34") (name "/EMI_D01") (class "Default")
      (node (ref "U1") (pin "43") (pinfunction "EMI_D01_43") (pintype "bidirectional"))
      (node (ref "U2") (pin "4") (pinfunction "DQ1_4") (pintype "bidirectional"))
    )
    (net (code "35") (name "/EMI_D02") (class "Default")
      (node (ref "U1") (pin "42") (pinfunction "EMI_D02_42") (pintype "bidirectional"))
      (node (ref "U2") (pin "5") (pinfunction "DQ2_5") (pintype "bidirectional"))
    )
    (net (code "36") (name "/EMI_D03") (class "Default")
      (node (ref "U1") (pin "44") (pinfunction "EMI_D03_44") (pintype "bidirectional"))
      (node (ref "U2") (pin "7") (pinfunction "DQ3_7") (pintype "bidirectional"))
    )
    (net (code "37") (name "/EMI_D04") (class "Default")
      (node (ref "U1") (pin "47") (pinfunction "EMI_D04_47") (pintype "bidirectional"))
      (node (ref "U2") (pin "8") (pinfunction "DQ4_8") (pintype "bidirectional"))
    )
    (net (code "38") (name "/EMI_D05") (class "Default")
      (node (ref "U1") (pin "48") (pinfunction "EMI_D05_48") (pintype "bidirectional"))
      (node (ref "U2") (pin "10") (pinfunction "DQ5_10") (pintype "bidirectional"))
    )
    (net (code "39") (name "/EMI_D06") (class "Default")
      (node (ref "U1") (pin "49") (pinfunction "EMI_D06_49") (pintype "bidirectional"))
      (node (ref "U2") (pin "11") (pinfunction "DQ6_11") (pintype "bidirectional"))
    )
    (net (code "40") (name "/EMI_D07") (class "Default")
      (node (ref "U1") (pin "50") (pinfunction "EMI_D07_50") (pintype "bidirectional"))
      (node (ref "U2") (pin "13") (pinfunction "DQ7_13") (pintype "bidirectional"))
    )
    (net (code "41") (name "/EMI_D08") (class "Default")
      (node (ref "U1") (pin "51") (pinfunction "EMI_D08_51") (pintype "bidirectional"))
      (node (ref "U2") (pin "54") (pinfunction "DQ8_54") (pintype "bidirectional"))
    )
    (net (code "42") (name "/EMI_D09") (class "Default")
      (node (ref "U1") (pin "52") (pinfunction "EMI_D09_52") (pintype "bidirectional"))
      (node (ref "U2") (pin "56") (pinfunction "DQ9_56") (pintype "bidirectional"))
    )
    (net (code "43") (name "/EMI_D10") (class "Default")
      (node (ref "U1") (pin "54") (pinfunction "EMI_D10_54") (pintype "bidirectional"))
      (node (ref "U2") (pin "57") (pinfunction "DQ10_57") (pintype "bidirectional"))
    )
    (net (code "44") (name "/EMI_D11") (class "Default")
      (node (ref "U1") (pin "55") (pinfunction "EMI_D11_55") (pintype "bidirectional"))
      (node (ref "U2") (pin "59") (pinfunction "DQ11_59") (pintype "bidirectional"))
    )
    (net (code "45") (name "/EMI_D12") (class "Default")
      (node (ref "U1") (pin "57") (pinfunction "EMI_D12_57") (pintype "bidirectional"))
      (node (ref "U2") (pin "60") (pinfunction "DQ12_60") (pintype "bidirectional"))
    )
    (net (code "46") (name "/EMI_D13") (class "Default")
      (node (ref "U1") (pin "58") (pinfunction "EMI_D13_58") (pintype "bidirectional"))
      (node (ref "U2") (pin "62") (pinfunction "DQ13_62") (pintype "bidirectional"))
    )
    (net (code "47") (name "/EMI_D14") (class "Default")
      (node (ref "U1") (pin "60") (pinfunction "EMI_D14_60") (pintype "bidirectional"))
      (node (ref "U2") (pin "63") (pinfunction "DQ14_63") (pintype "bidirectional"))
    )
    (net (code "48") (name "/EMI_D15") (class "Default")
      (node (ref "U1") (pin "59") (pinfunction "EMI_D15_59") (pintype "bidirectional"))
      (node (ref "U2") (pin "65") (pinfunction "DQ15_65") (pintype "bidirectional"))
    )
    (net (code "49") (name "/EMI_DQM0") (class "Default")
      (node (ref "U1") (pin "46") (pinfunction "EMI_DQM0_46") (pintype "output"))
      (node (ref "U2") (pin "20") (pinfunction "LDM_20") (pintype "input"))
    )
    (net (code "50") (name "/EMI_DQM1") (class "Default")
      (node (ref "U1") (pin "56") (pinfunction "EMI_DQM1_56") (pintype "output"))
      (node (ref "U2") (pin "47") (pinfunction "UDM_47") (pintype "input"))
    )
    (net (code "51") (name "/EMI_DQS0") (class "Default")
      (node (ref "U1") (pin "39") (pinfunction "EMI_DQS0_39") (pintype "output"))
      (node (ref "U2") (pin "16") (pinfunction "LDQS_16") (pintype "bidirectional"))
    )
    (net (code "52") (name "/EMI_DQS1") (class "Default")
      (node (ref "U1") (pin "40") (pinfunction "EMI_DQS1_40") (pintype "output"))
      (node (ref "U2") (pin "51") (pinfunction "UDQS_51") (pintype "input"))
    )
    (net (code "53") (name "/EMI_RASN") (class "Default")
      (node (ref "U1") (pin "62") (pinfunction "EMI_RASN_62") (pintype "output"))
      (node (ref "U2") (pin "23") (pinfunction "#RAS_23") (pintype "input"))
    )
    (net (code "54") (name "/EMI_WEN") (class "Default")
      (node (ref "U1") (pin "77") (pinfunction "EMI_WEN_77") (pintype "output"))
      (node (ref "U2") (pin "21") (pinfunction "#WE_21") (pintype "input"))
    )
    (net (code "55") (name "/GPMI_ALE") (class "Default")
      (node (ref "U1") (pin "20") (pinfunction "GPMI_ALE/LCD_D17_20") (pintype "bidirectional"))
      (node (ref "U3") (pin "17") (pinfunction "ALE_17") (pintype "input"))
    )
    (net (code "56") (name "/GPMI_CE0N") (class "Default")
      (node (ref "R14") (pin "1") (pinfunction "1_1") (pintype "passive"))
      (node (ref "U1") (pin "82") (pinfunction "GPMI_CE0N_82") (pintype "bidirectional"))
      (node (ref "U3") (pin "9") (pinfunction "#CE_9") (pintype "input"))
    )
    (net (code "57") (name "/GPMI_CLE") (class "Default")
      (node (ref "U1") (pin "19") (pinfunction "GPMI_CLE/LCD_D16_19") (pintype "bidirectional"))
      (node (ref "U3") (pin "16") (pinfunction "CLE_16") (pintype "input"))
    )
    (net (code "58") (name "/GPMI_D00") (class "Default")
      (node (ref "U1") (pin "22") (pinfunction "GPMI_D00/LCD_D08/SSP2_DATA0_22") (pintype "bidirectional"))
      (node (ref "U3") (pin "29") (pinfunction "I/O0_29") (pintype "bidirectional"))
    )
    (net (code "59") (name "/GPMI_D01") (class "Default")
      (node (ref "U1") (pin "23") (pinfunction "GPMI_D01/LCD_D09/SSP2_DATA1_23") (pintype "bidirectional"))
      (node (ref "U3") (pin "30") (pinfunction "I/O1_30") (pintype "bidirectional"))
    )
    (net (code "60") (name "/GPMI_D02") (class "Default")
      (node (ref "U1") (pin "24") (pinfunction "GPMI_D02/LCD_D10/SSP2_DATA2_24") (pintype "bidirectional"))
      (node (ref "U3") (pin "31") (pinfunction "I/O2_31") (pintype "bidirectional"))
    )
    (net (code "61") (name "/GPMI_D03") (class "Default")
      (node (ref "U1") (pin "25") (pinfunction "GPMI_D03/LCD_D11/SSP2_DATA3_25") (pintype "bidirectional"))
      (node (ref "U3") (pin "32") (pinfunction "I/O3_32") (pintype "bidirectional"))
    )
    (net (code "62") (name "/GPMI_D04") (class "Default")
      (node (ref "U1") (pin "27") (pinfunction "GPMI_D04/LCD_D12/SSP2_DATA4_27") (pintype "bidirectional"))
      (node (ref "U3") (pin "41") (pinfunction "I/O4_41") (pintype "bidirectional"))
    )
    (net (code "63") (name "/GPMI_D05") (class "Default")
      (node (ref "U1") (pin "26") (pinfunction "GPMI_D05/LCD_D13/SSP2_DATA5_26") (pintype "bidirectional"))
      (node (ref "U3") (pin "42") (pinfunction "I/O5_42") (pintype "bidirectional"))
    )
    (net (code "64") (name "/GPMI_D06") (class "Default")
      (node (ref "U1") (pin "29") (pinfunction "GPMI_D06/LCD_D14/SSP2_DATA6_29") (pintype "bidirectional"))
      (node (ref "U3") (pin "43") (pinfunction "I/O6_43") (pintype "bidirectional"))
    )
    (net (code "65") (name "/GPMI_D07") (class "Default")
      (node (ref "U1") (pin "28") (pinfunction "GPMI_D07/LCD_D15/SSP2_DATA7_28") (pintype "bidirectional"))
      (node (ref "U3") (pin "44") (pinfunction "I/O7_44") (pintype "bidirectional"))
    )
    (net (code "66") (name "/GPMI_RDN") (class "Default")
      (node (ref "U1") (pin "31") (pinfunction "GPMI_RDN_31") (pintype "bidirectional"))
      (node (ref "U3") (pin "8") (pinfunction "#RE_8") (pintype "input"))
    )
    (net (code "67") (name "/GPMI_RDY0") (class "Default")
      (node (ref "R13") (pin "1") (pinfunction "1_1") (pintype "passive"))
      (node (ref "U1") (pin "32") (pinfunction "GPMI_RDY0/SSP2_DETECT_32") (pintype "bidirectional"))
      (node (ref "U3") (pin "7") (pinfunction "R/#B_7") (pintype "output"))
    )
    (net (code "68") (name "/GPMI_WPN") (class "Default")
      (node (ref "R15") (pin "2") (pinfunction "2_2") (pintype "passive"))
      (node (ref "U1") (pin "34") (pinfunction "GPMI_WPN_34") (pintype "bidirectional"))
      (node (ref "U3") (pin "19") (pinfunction "#WP_19") (pintype "input"))
    )
    (net (code "69") (name "/GPMI_WRN") (class "Default")
      (node (ref "U1") (pin "33") (pinfunction "GPMI_WRN/SSP2_SCK_33") (pintype "bidirectional"))
      (node (ref "U3") (pin "18") (pinfunction "#WE_18") (pintype "input"))
    )
    (net (code "70") (name "/HP_VGND") (class "Default")
      (node (ref "U1") (pin "111") (pinfunction "HP_VGND_111") (pintype "power_in"))
    )
    (net (code "71") (name "/I2C_SCL") (class "Default")
      (node (ref "U1") (pin "11") (pinfunction "LCD_ENABLE/I2C_SCL_11") (pintype "bidirectional"))
    )
    (net (code "72") (name "/I2C_SDA") (class "Default")
      (node (ref "U1") (pin "15") (pinfunction "LCD_HSYNC/I2C_SDA_15") (pintype "bidirectional"))
    )
    (net (code "73") (name "/LCD_D00") (class "Default")
      (node (ref "R23") (pin "2") (pinfunction "2_2") (pintype "passive"))
      (node (ref "R27") (pin "2") (pinfunction "2_2") (pintype "passive"))
      (node (ref "U1") (pin "2") (pinfunction "LCD_D00_2") (pintype "bidirectional"))
    )
    (net (code "74") (name "/LCD_D01") (class "Default")
      (node (ref "R22") (pin "2") (pinfunction "2_2") (pintype "passive"))
      (node (ref "R26") (pin "2") (pinfunction "2_2") (pintype "passive"))
      (node (ref "U1") (pin "3") (pinfunction "LCD_D01_3") (pintype "bidirectional"))
    )
    (net (code "75") (name "/LCD_D02") (class "Default")
      (node (ref "R21") (pin "2") (pinfunction "2_2") (pintype "passive"))
      (node (ref "R25") (pin "2") (pinfunction "2_2") (pintype "passive"))
      (node (ref "U1") (pin "4") (pinfunction "LCD_D02_4") (pintype "bidirectional"))
    )
    (net (code "76") (name "/LCD_D03") (class "Default")
      (node (ref "R20") (pin "2") (pinfunction "2_2") (pintype "passive"))
      (node (ref "R24") (pin "2") (pinfunction "2_2") (pintype "passive"))
      (node (ref "U1") (pin "5") (pinfunction "LCD_D03_5") (pintype "bidirectional"))
    )
    (net (code "77") (name "/NFDX_LED") (class "Default")
      (node (ref "LED1") (pin "C") (pinfunction "C_C") (pintype "passive"))
      (node (ref "U4") (pin "20") (pinfunction "NFDX_LED/GPIO0_20") (pintype "bidirectional"))
    )
    (net (code "78") (name "/NFDX_LED_2") (class "Default")
      (node (ref "LED4") (pin "C") (pinfunction "C_C") (pintype "passive"))
      (node (ref "U5") (pin "26") (pinfunction "NFDX_LED/GPIO8_26") (pintype "bidirectional"))
    )
    (net (code "79") (name "/NLNKA_LED") (class "Default")
      (node (ref "RJ1") (pin "Y+") (pinfunction "Y+_Y+") (pintype "bidirectional"))
      (node (ref "U4") (pin "21") (pinfunction "NLNKA_LED/GPIO1_21") (pintype "bidirectional"))
    )
    (net (code "80") (name "/NLNKA_LED_2") (class "Default")
      (node (ref "RJ2") (pin "Y+") (pinfunction "Y+_Y+") (pintype "bidirectional"))
      (node (ref "U5") (pin "27") (pinfunction "NLNKA_LED/GPIO9_27") (pintype "bidirectional"))
    )
    (net (code "81") (name "/NSPD_LED") (class "Default")
      (node (ref "RJ1") (pin "G+") (pinfunction "G+_G+") (pintype "bidirectional"))
      (node (ref "U4") (pin "22") (pinfunction "NSPD_LED/GPIO2_22") (pintype "bidirectional"))
    )
    (net (code "82") (name "/NSPD_LED_2") (class "Default")
      (node (ref "RJ2") (pin "G+") (pinfunction "G+_G+") (pintype "bidirectional"))
      (node (ref "U5") (pin "28") (pinfunction "NSPD_LED/GPIO10_28") (pintype "bidirectional"))
    )
    (net (code "83") (name "/PRTCTL2") (class "Default")
      (node (ref "U4") (pin "14") (pinfunction "PRTCTL2_14") (pintype "passive"))
      (node (ref "U6") (pin "1") (pinfunction "ENA_1") (pintype "input"))
      (node (ref "U6") (pin "2") (pinfunction "FLAG_A_2") (pintype "open_collector"))
    )
    (net (code "84") (name "/PRTCTL3") (class "Default")
      (node (ref "U4") (pin "16") (pinfunction "PRTCTL3_16") (pintype "passive"))
      (node (ref "U6") (pin "3") (pinfunction "FLAG_B_3") (pintype "open_collector"))
      (node (ref "U6") (pin "4") (pinfunction "ENB_4") (pintype "input"))
    )
    (net (code "85") (name "/PSWITCH") (class "Default")
      (node (ref "C5") (pin "1") (pinfunction "1_1") (pintype "passive"))
      (node (ref "R2") (pin "2") (pinfunction "2_2") (pintype "passive"))
      (node (ref "U1") (pin "119") (pinfunction "PSWITCH_119") (pintype "input"))
    )
    (net (code "86") (name "/RXN") (class "Default")
      (node (ref "C72") (pin "1") (pinfunction "1_1") (pintype "passive"))
      (node (ref "R29") (pin "2") (pinfunction "2_2") (pintype "passive"))
      (node (ref "RJ1") (pin "RD-") (pinfunction "RD-_RD-") (pintype "bidirectional"))
      (node (ref "U4") (pin "53") (pinfunction "RXN_53") (pintype "passive"))
    )
    (net (code "87") (name "/RXN_2") (class "Default")
      (node (ref "C81") (pin "1") (pinfunction "1_1") (pintype "passive"))
      (node (ref "R45") (pin "2") (pinfunction "2_2") (pintype "passive"))
      (node (ref "RJ2") (pin "RD-") (pinfunction "RD-_RD-") (pintype "bidirectional"))
      (node (ref "U5") (pin "5") (pinfunction "RXN_5") (pintype "bidirectional"))
    )
    (net (code "88") (name "/RXP") (class "Default")
      (node (ref "C70") (pin "1") (pinfunction "1_1") (pintype "passive"))
      (node (ref "R30") (pin "2") (pinfunction "2_2") (pintype "passive"))
      (node (ref "RJ1") (pin "RD+") (pinfunction "RD+_RD+") (pintype "bidirectional"))
      (node (ref "U4") (pin "52") (pinfunction "RXP_52") (pintype "passive"))
    )
    (net (code "89") (name "/RXP_2") (class "Default")
      (node (ref "C79") (pin "1") (pinfunction "1_1") (pintype "passive"))
      (node (ref "R46") (pin "2") (pinfunction "2_2") (pintype "passive"))
      (node (ref "RJ2") (pin "RD+") (pinfunction "RD+_RD+") (pintype "bidirectional"))
      (node (ref "U5") (pin "6") (pinfunction "RXP_6") (pintype "bidirectional"))
    )
    (net (code "90") (name "/SSP1_CMD") (class "Default")
      (node (ref "R11") (pin "1") (pinfunction "1_1") (pintype "passive"))
      (node (ref "SD") (pin "3") (pinfunction "CMD_3") (pintype "bidirectional"))
      (node (ref "U1") (pin "83") (pinfunction "SSP1_CMD/SPI1_MOSI/JTAG_TDO_83") (pintype "bidirectional"))
    )
    (net (code "91") (name "/SSP1_DATA0") (class "Default")
      (node (ref "R10") (pin "1") (pinfunction "1_1") (pintype "passive"))
      (node (ref "SD") (pin "7") (pinfunction "DAT0_7") (pintype "bidirectional"))
      (node (ref "U1") (pin "84") (pinfunction "SSP1_DATA0/SPI1_MISO/JTAG_TDI_84") (pintype "bidirectional"))
    )
    (net (code "92") (name "/SSP1_DATA1") (class "Default")
      (node (ref "R9") (pin "1") (pinfunction "1_1") (pintype "passive"))
      (node (ref "SD") (pin "8") (pinfunction "DAT1_8") (pintype "bidirectional"))
      (node (ref "U1") (pin "85") (pinfunction "SSP1_DATA1/I2C_SCL/JTAG_TCLK_85") (pintype "bidirectional"))
    )
    (net (code "93") (name "/SSP1_DATA2") (class "Default")
      (node (ref "R8") (pin "1") (pinfunction "1_1") (pintype "passive"))
      (node (ref "SD") (pin "1") (pinfunction "DAT2_1") (pintype "bidirectional"))
      (node (ref "U1") (pin "86") (pinfunction "SSP1_DATA2/I2C_SDA/JTAG_RTCK_86") (pintype "bidirectional"))
    )
    (net (code "94") (name "/SSP1_DATA3") (class "Default")
      (node (ref "R12") (pin "2") (pinfunction "2_2") (pintype "passive"))
      (node (ref "SD") (pin "2") (pinfunction "CD/DAT3_2") (pintype "bidirectional"))
      (node (ref "U1") (pin "87") (pinfunction "SSP1_DATA3/SPI1_SS#/JTAG_TMS_87") (pintype "bidirectional"))
    )
    (net (code "95") (name "/SSP1_SCK") (class "Default")
      (node (ref "SD") (pin "5") (pinfunction "CLK_5") (pintype "bidirectional"))
      (node (ref "U1") (pin "90") (pinfunction "SSP1_SCK/SPI1_SCK/JTAG_TRST_90") (pintype "bidirectional"))
    )
    (net (code "96") (name "/TXN") (class "Default")
      (node (ref "C69") (pin "1") (pinfunction "1_1") (pintype "passive"))
      (node (ref "R31") (pin "2") (pinfunction "2_2") (pintype "passive"))
      (node (ref "RJ1") (pin "TD-") (pinfunction "TD-_TD-") (pintype "bidirectional"))
      (node (ref "U4") (pin "56") (pinfunction "TXN_56") (pintype "passive"))
    )
    (net (code "97") (name "/TXN_2") (class "Default")
      (node (ref "C78") (pin "1") (pinfunction "1_1") (pintype "passive"))
      (node (ref "R47") (pin "2") (pinfunction "2_2") (pintype "passive"))
      (node (ref "RJ2") (pin "TD-") (pinfunction "TD-_TD-") (pintype "bidirectional"))
      (node (ref "U5") (pin "2") (pinfunction "TXN_2") (pintype "bidirectional"))
    )
    (net (code "98") (name "/TXP") (class "Default")
      (node (ref "C71") (pin "1") (pinfunction "1_1") (pintype "passive"))
      (node (ref "R32") (pin "2") (pinfunction "2_2") (pintype "passive"))
      (node (ref "RJ1") (pin "TD+") (pinfunction "TD+_TD+") (pintype "bidirectional"))
      (node (ref "U4") (pin "55") (pinfunction "TXP_55") (pintype "passive"))
    )
    (net (code "99") (name "/TXP_2") (class "Default")
      (node (ref "C80") (pin "1") (pinfunction "1_1") (pintype "passive"))
      (node (ref "R48") (pin "2") (pinfunction "2_2") (pintype "passive"))
      (node (ref "RJ2") (pin "TD+") (pinfunction "TD+_TD+") (pintype "bidirectional"))
      (node (ref "U5") (pin "3") (pinfunction "TXP_3") (pintype "bidirectional"))
    )
    (net (code "100") (name "/USB_DM") (class "Default")
      (node (ref "U1") (pin "123") (pinfunction "USB_DM_123") (pintype "bidirectional"))
      (node (ref "U4") (pin "58") (pinfunction "USBDM0_58") (pintype "passive"))
    )
    (net (code "101") (name "/USB_DM2") (class "Default")
      (node (ref "U4") (pin "1") (pinfunction "USBDM2_1") (pintype "passive"))
      (node (ref "X1") (pin "2") (pinfunction "2_2") (pintype "passive"))
    )
    (net (code "102") (name "/USB_DM3") (class "Default")
      (node (ref "U4") (pin "3") (pinfunction "USBDM3_3") (pintype "passive"))
      (node (ref "U5") (pin "11") (pinfunction "USBDM_11") (pintype "bidirectional"))
    )
    (net (code "103") (name "/USB_DP") (class "Default")
      (node (ref "U1") (pin "124") (pinfunction "USB_DP_124") (pintype "bidirectional"))
      (node (ref "U4") (pin "59") (pinfunction "USBDP0_59") (pintype "passive"))
    )
    (net (code "104") (name "/USB_DP2") (class "Default")
      (node (ref "U4") (pin "2") (pinfunction "USBDP2_2") (pintype "passive"))
      (node (ref "X1") (pin "3") (pinfunction "3_3") (pintype "passive"))
    )
    (net (code "105") (name "/USB_DP3") (class "Default")
      (node (ref "U4") (pin "4") (pinfunction "USBDP3_4") (pintype "passive"))
      (node (ref "U5") (pin "12") (pinfunction "USBDP_12") (pintype "bidirectional"))
    )
    (net (code "106") (name "/USB_PWRA") (class "Default")
      (node (ref "R41") (pin "2") (pinfunction "2_2") (pintype "passive"))
      (node (ref "U6") (pin "8") (pinfunction "OUT_A_8") (pintype "output"))
      (node (ref "X1") (pin "1") (pinfunction "1_1") (pintype "passive"))
    )
    (net (code "107") (name "/USB_PWRB") (class "Default")
      (node (ref "R40") (pin "2") (pinfunction "2_2") (pintype "passive"))
      (node (ref "U6") (pin "5") (pinfunction "OUT_B_5") (pintype "output"))
    )
    (net (code "108") (name "/VDD3V3A") (class "Default")
      (node (ref "C54") (pin "1") (pinfunction "1_1") (pintype "passive"))
      (node (ref "C55") (pin "1") (pinfunction "1_1") (pintype "passive"))
      (node (ref "C56") (pin "1") (pinfunction "1_1") (pintype "passive"))
      (node (ref "C57") (pin "1") (pinfunction "1_1") (pintype "passive"))
      (node (ref "C58") (pin "1") (pinfunction "1_1") (pintype "passive"))
      (node (ref "C7") (pin "1") (pinfunction "1_1") (pintype "passive"))
      (node (ref "C8") (pin "1") (pinfunction "1_1") (pintype "passive"))
      (node (ref "C86") (pin "1") (pinfunction "1_1") (pintype "passive"))
      (node (ref "C87") (pin "1") (pinfunction "1_1") (pintype "passive"))
      (node (ref "C88") (pin "1") (pinfunction "1_1") (pintype "passive"))
      (node (ref "C89") (pin "1") (pinfunction "1_1") (pintype "passive"))
      (node (ref "L1") (pin "2") (pinfunction "2_2") (pintype "passive"))
      (node (ref "L6") (pin "2") (pinfunction "2_2") (pintype "passive"))
      (node (ref "R28") (pin "1") (pinfunction "1_1") (pintype "passive"))
      (node (ref "R29") (pin "1") (pinfunction "1_1") (pintype "passive"))
      (node (ref "R30") (pin "1") (pinfunction "1_1") (pintype "passive"))
      (node (ref "R31") (pin "1") (pinfunction "1_1") (pintype "passive"))
      (node (ref "R32") (pin "1") (pinfunction "1_1") (pintype "passive"))
      (node (ref "R44") (pin "1") (pinfunction "1_1") (pintype "passive"))
      (node (ref "R45") (pin "1") (pinfunction "1_1") (pintype "passive"))
      (node (ref "R46") (pin "1") (pinfunction "1_1") (pintype "passive"))
      (node (ref "R47") (pin "1") (pinfunction "1_1") (pintype "passive"))
      (node (ref "R48") (pin "1") (pinfunction "1_1") (pintype "passive"))
      (node (ref "U4") (pin "10") (pinfunction "VDD33A_3_10") (pintype "power_in"))
      (node (ref "U4") (pin "49") (pinfunction "VDD33A_4_49") (pintype "power_in"))
      (node (ref "U4") (pin "5") (pinfunction "VDD33A_2_5") (pintype "power_in"))
      (node (ref "U4") (pin "51") (pinfunction "VDD33A_5_51") (pintype "power_in"))
      (node (ref "U4") (pin "54") (pinfunction "VDD33A_6_54") (pintype "power_in"))
      (node (ref "U4") (pin "57") (pinfunction "VDD33A_7_57") (pintype "power_in"))
      (node (ref "U4") (pin "64") (pinfunction "VDD33A_64") (pintype "power_in"))
      (node (ref "U5") (pin "15") (pinfunction "VDD33A_3_15") (pintype "power_in"))
      (node (ref "U5") (pin "4") (pinfunction "VDD33A_4") (pintype "power_in"))
      (node (ref "U5") (pin "9") (pinfunction "VDD33A_2_9") (pintype "power_in"))
    )
    (net (code "109") (name "/VDD4P2") (class "Default")
      (node (ref "C16") (pin "1") (pinfunction "1_1") (pintype "passive"))
      (node (ref "C17") (pin "1") (pinfunction "1_1") (pintype "passive"))
      (node (ref "D1") (pin "C") (pinfunction "C_C") (pintype "passive"))
      (node (ref "U1") (pin "101") (pinfunction "VDD4P2_101") (pintype "power_in"))
    )
    (net (code "110") (name "/VDD18CORE") (class "Default")
      (node (ref "C59") (pin "1") (pinfunction "1_1") (pintype "passive"))
      (node (ref "C60") (pin "1") (pinfunction "1_1") (pintype "passive"))
      (node (ref "C61") (pin "1") (pinfunction "1_1") (pintype "passive"))
      (node (ref "U4") (pin "15") (pinfunction "VDD18CORE_2_15") (pintype "power_in"))
      (node (ref "U4") (pin "38") (pinfunction "VDD18CORE_38") (pintype "power_in"))
    )
    (net (code "111") (name "/VDD18ETHPLL") (class "Default")
      (node (ref "C67") (pin "1") (pinfunction "1_1") (pintype "passive"))
      (node (ref "L4") (pin "2") (pinfunction "2_2") (pintype "passive"))
      (node (ref "U4") (pin "48") (pinfunction "VDD18ETHPLL_48") (pintype "power_in"))
    )
    (net (code "112") (name "/VDD18USBPLL") (class "Default")
      (node (ref "C68") (pin "1") (pinfunction "1_1") (pintype "passive"))
      (node (ref "L4") (pin "1") (pinfunction "1_1") (pintype "passive"))
      (node (ref "U4") (pin "62") (pinfunction "VDD18USBPLL_62") (pintype "power_in"))
    )
    (net (code "113") (name "/VDDCORE") (class "Default")
      (node (ref "C83") (pin "1") (pinfunction "1_1") (pintype "passive"))
      (node (ref "C95") (pin "1") (pinfunction "1_1") (pintype "passive"))
      (node (ref "C96") (pin "1") (pinfunction "1_1") (pintype "passive"))
      (node (ref "C97") (pin "1") (pinfunction "1_1") (pintype "passive"))
      (node (ref "L5") (pin "1") (pinfunction "1_1") (pintype "passive"))
      (node (ref "L7") (pin "1") (pinfunction "1_1") (pintype "passive"))
      (node (ref "U5") (pin "21") (pinfunction "VDDCORE_21") (pintype "bidirectional"))
      (node (ref "U5") (pin "50") (pinfunction "VDDCORE_50") (pintype "power_in"))
    )
    (net (code "114") (name "/VDDIO_DRAM") (class "Default")
      (node (ref "C13") (pin "1") (pinfunction "1_1") (pintype "passive"))
      (node (ref "C14") (pin "1") (pinfunction "1_1") (pintype "passive"))
      (node (ref "C44") (pin "2") (pinfunction "2_2") (pintype "passive"))
      (node (ref "C45") (pin "2") (pinfunction "2_2") (pintype "passive"))
      (node (ref "C46") (pin "2") (pinfunction "2_2") (pintype "passive"))
      (node (ref "C47") (pin "2") (pinfunction "2_2") (pintype "passive"))
      (node (ref "C48") (pin "2") (pinfunction "2_2") (pintype "passive"))
      (node (ref "C49") (pin "2") (pinfunction "2_2") (pintype "passive"))
      (node (ref "C50") (pin "2") (pinfunction "2_2") (pintype "passive"))
      (node (ref "C51") (pin "2") (pinfunction "2_2") (pintype "passive"))
      (node (ref "C52") (pin "2") (pinfunction "2_2") (pintype "passive"))
      (node (ref "R17") (pin "2") (pinfunction "2_2") (pintype "passive"))
      (node (ref "R18") (pin "2") (pinfunction "2_2") (pintype "passive"))
      (node (ref "U1") (pin "38") (pinfunction "VDDIO_EMIQ_38") (pintype "power_in"))
      (node (ref "U1") (pin "45") (pinfunction "VDDIO_EMI1_45") (pintype "power_in"))
      (node (ref "U1") (pin "53") (pinfunction "VDDIO_EMI2_53") (pintype "power_in"))
      (node (ref "U2") (pin "1") (pinfunction "VDD1_1") (pintype "power_in"))
      (node (ref "U2") (pin "15") (pinfunction "VDDQ3_15") (pintype "power_in"))
      (node (ref "U2") (pin "18") (pinfunction "VDD2_18") (pintype "power_in"))
      (node (ref "U2") (pin "3") (pinfunction "VDDQ1_3") (pintype "power_in"))
      (node (ref "U2") (pin "33") (pinfunction "VDD3_33") (pintype "power_in"))
      (node (ref "U2") (pin "55") (pinfunction "VDDQ4_55") (pintype "power_in"))
      (node (ref "U2") (pin "61") (pinfunction "VDDQ5_61") (pintype "power_in"))
      (node (ref "U2") (pin "9") (pinfunction "VDDQ2_9") (pintype "power_in"))
    )
    (net (code "115") (name "/VDDM{slash}LRADC4") (class "Default")
      (node (ref "C15") (pin "1") (pinfunction "1_1") (pintype "passive"))
      (node (ref "U1") (pin "106") (pinfunction "VDDM/LRADC4_106") (pintype "power_in"))
    )
    (net (code "116") (name "/VDDPLL2") (class "Default")
      (node (ref "C99") (pin "1") (pinfunction "1_1") (pintype "passive"))
      (node (ref "L7") (pin "2") (pinfunction "2_2") (pintype "passive"))
      (node (ref "U5") (pin "10") (pinfunction "VDDPLL_10") (pintype "power_in"))
    )
    (net (code "117") (name "/VDDXTAL") (class "Default")
      (node (ref "C34") (pin "1") (pinfunction "1_1") (pintype "passive"))
      (node (ref "S1") (pin "3") (pinfunction "P_3") (pintype "passive"))
      (node (ref "S1") (pin "4") (pinfunction "P1_4") (pintype "passive"))
      (node (ref "U1") (pin "120") (pinfunction "VDDXTAL_120") (pintype "passive"))
    )
    (net (code "118") (name "/XI") (class "Default")
      (node (ref "C84") (pin "1") (pinfunction "1_1") (pintype "passive"))
      (node (ref "Q3") (pin "1") (pinfunction "1_1") (pintype "passive"))
      (node (ref "U5") (pin "18") (pinfunction "XI_18") (pintype "input"))
    )
    (net (code "119") (name "/XTALI") (class "Default")
      (node (ref "C35") (pin "2") (pinfunction "2_2") (pintype "passive"))
      (node (ref "Q1") (pin "2") (pinfunction "2_2") (pintype "passive"))
      (node (ref "T1") (pin "3") (pinfunction "C_3") (pintype "passive"))
      (node (ref "U1") (pin "122") (pinfunction "XTALI_122") (pintype "input"))
    )
    (net (code "120") (name "/XTALO") (class "Default")
      (node (ref "C36") (pin "2") (pinfunction "2_2") (pintype "passive"))
      (node (ref "Q1") (pin "1") (pinfunction "1_1") (pintype "passive"))
      (node (ref "T2") (pin "3") (pinfunction "C_3") (pintype "passive"))
      (node (ref "U1") (pin "121") (pinfunction "XTALO_121") (pintype "output"))
    )
    (net (code "121") (name "GND") (class "Default")
      (node (ref "C1") (pin "2") (pinfunction "2_2") (pintype "passive"))
      (node (ref "C10") (pin "2") (pinfunction "2_2") (pintype "passive"))
      (node (ref "C11") (pin "2") (pinfunction "2_2") (pintype "passive"))
      (node (ref "C12") (pin "2") (pinfunction "2_2") (pintype "passive"))
      (node (ref "C13") (pin "2") (pinfunction "2_2") (pintype "passive"))
      (node (ref "C14") (pin "2") (pinfunction "2_2") (pintype "passive"))
      (node (ref "C15") (pin "2") (pinfunction "2_2") (pintype "passive"))
      (node (ref "C16") (pin "2") (pinfunction "2_2") (pintype "passive"))
      (node (ref "C17") (pin "2") (pinfunction "2_2") (pintype "passive"))
      (node (ref "C18") (pin "2") (pinfunction "2_2") (pintype "passive"))
      (node (ref "C19") (pin "2") (pinfunction "2_2") (pintype "passive"))
      (node (ref "C2") (pin "2") (pinfunction "2_2") (pintype "passive"))
      (node (ref "C20") (pin "2") (pinfunction "2_2") (pintype "passive"))
      (node (ref "C21") (pin "2") (pinfunction "2_2") (pintype "passive"))
      (node (ref "C22") (pin "2") (pinfunction "2_2") (pintype "passive"))
      (node (ref "C23") (pin "2") (pinfunction "2_2") (pintype "passive"))
      (node (ref "C24") (pin "2") (pinfunction "2_2") (pintype "passive"))
      (node (ref "C25") (pin "2") (pinfunction "2_2") (pintype "passive"))
      (node (ref "C26") (pin "2") (pinfunction "2_2") (pintype "passive"))
      (node (ref "C27") (pin "2") (pinfunction "2_2") (pintype "passive"))
      (node (ref "C28") (pin "2") (pinfunction "2_2") (pintype "passive"))
      (node (ref "C29") (pin "2") (pinfunction "2_2") (pintype "passive"))
      (node (ref "C3") (pin "-") (pinfunction "-_-") (pintype "passive"))
      (node (ref "C30") (pin "2") (pinfunction "2_2") (pintype "passive"))
      (node (ref "C31") (pin "2") (pinfunction "2_2") (pintype "passive"))
      (node (ref "C32") (pin "2") (pinfunction "2_2") (pintype "passive"))
      (node (ref "C33") (pin "2") (pinfunction "2_2") (pintype "passive"))
      (node (ref "C34") (pin "2") (pinfunction "2_2") (pintype "passive"))
      (node (ref "C35") (pin "1") (pinfunction "1_1") (pintype "passive"))
      (node (ref "C36") (pin "1") (pinfunction "1_1") (pintype "passive"))
      (node (ref "C37") (pin "2") (pinfunction "2_2") (pintype "passive"))
      (node (ref "C38") (pin "2") (pinfunction "2_2") (pintype "passive"))
      (node (ref "C39") (pin "1") (pinfunction "1_1") (pintype "passive"))
      (node (ref "C4") (pin "-") (pinfunction "-_-") (pintype "passive"))
      (node (ref "C40") (pin "1") (pinfunction "1_1") (pintype "passive"))
      (node (ref "C41") (pin "1") (pinfunction "1_1") (pintype "passive"))
      (node (ref "C42") (pin "1") (pinfunction "1_1") (pintype "passive"))
      (node (ref "C43") (pin "1") (pinfunction "1_1") (pintype "passive"))
      (node (ref "C44") (pin "1") (pinfunction "1_1") (pintype "passive"))
      (node (ref "C45") (pin "1") (pinfunction "1_1") (pintype "passive"))
      (node (ref "C46") (pin "1") (pinfunction "1_1") (pintype "passive"))
      (node (ref "C47") (pin "1") (pinfunction "1_1") (pintype "passive"))
      (node (ref "C48") (pin "1") (pinfunction "1_1") (pintype "passive"))
      (node (ref "C49") (pin "1") (pinfunction "1_1") (pintype "passive"))
      (node (ref "C5") (pin "2") (pinfunction "2_2") (pintype "passive"))
      (node (ref "C50") (pin "1") (pinfunction "1_1") (pintype "passive"))
      (node (ref "C51") (pin "1") (pinfunction "1_1") (pintype "passive"))
      (node (ref "C53") (pin "1") (pinfunction "1_1") (pintype "passive"))
      (node (ref "C54") (pin "2") (pinfunction "2_2") (pintype "passive"))
      (node (ref "C55") (pin "2") (pinfunction "2_2") (pintype "passive"))
      (node (ref "C56") (pin "2") (pinfunction "2_2") (pintype "passive"))
      (node (ref "C57") (pin "2") (pinfunction "2_2") (pintype "passive"))
      (node (ref "C58") (pin "2") (pinfunction "2_2") (pintype "passive"))
      (node (ref "C59") (pin "2") (pinfunction "2_2") (pintype "passive"))
      (node (ref "C6") (pin "2") (pinfunction "2_2") (pintype "passive"))
      (node (ref "C60") (pin "2") (pinfunction "2_2") (pintype "passive"))
      (node (ref "C61") (pin "2") (pinfunction "2_2") (pintype "passive"))
      (node (ref "C62") (pin "2") (pinfunction "2_2") (pintype "passive"))
      (node (ref "C63") (pin "2") (pinfunction "2_2") (pintype "passive"))
      (node (ref "C64") (pin "2") (pinfunction "2_2") (pintype "passive"))
      (node (ref "C65") (pin "2") (pinfunction "2_2") (pintype "passive"))
      (node (ref "C66") (pin "2") (pinfunction "2_2") (pintype "passive"))
      (node (ref "C67") (pin "2") (pinfunction "2_2") (pintype "passive"))
      (node (ref "C68") (pin "2") (pinfunction "2_2") (pintype "passive"))
      (node (ref "C69") (pin "2") (pinfunction "2_2") (pintype "passive"))
      (node (ref "C7") (pin "2") (pinfunction "2_2") (pintype "passive"))
      (node (ref "C70") (pin "2") (pinfunction "2_2") (pintype "passive"))
      (node (ref "C71") (pin "2") (pinfunction "2_2") (pintype "passive"))
      (node (ref "C72") (pin "2") (pinfunction "2_2") (pintype "passive"))
      (node (ref "C73") (pin "2") (pinfunction "2_2") (pintype "passive"))
      (node (ref "C74") (pin "2") (pinfunction "2_2") (pintype "passive"))
      (node (ref "C75") (pin "2") (pinfunction "2_2") (pintype "passive"))
      (node (ref "C76") (pin "2") (pinfunction "2_2") (pintype "passive"))
      (node (ref "C77") (pin "1") (pinfunction "1_1") (pintype "passive"))
      (node (ref "C78") (pin "2") (pinfunction "2_2") (pintype "passive"))
      (node (ref "C79") (pin "2") (pinfunction "2_2") (pintype "passive"))
      (node (ref "C8") (pin "2") (pinfunction "2_2") (pintype "passive"))
      (node (ref "C80") (pin "2") (pinfunction "2_2") (pintype "passive"))
      (node (ref "C81") (pin "2") (pinfunction "2_2") (pintype "passive"))
      (node (ref "C82") (pin "2") (pinfunction "2_2") (pintype "passive"))
      (node (ref "C83") (pin "2") (pinfunction "2_2") (pintype "passive"))
      (node (ref "C84") (pin "2") (pinfunction "2_2") (pintype "passive"))
      (node (ref "C85") (pin "2") (pinfunction "2_2") (pintype "passive"))
      (node (ref "C86") (pin "2") (pinfunction "2_2") (pintype "passive"))
      (node (ref "C87") (pin "2") (pinfunction "2_2") (pintype "passive"))
      (node (ref "C88") (pin "2") (pinfunction "2_2") (pintype "passive"))
      (node (ref "C89") (pin "2") (pinfunction "2_2") (pintype "passive"))
      (node (ref "C9") (pin "2") (pinfunction "2_2") (pintype "passive"))
      (node (ref "C90") (pin "2") (pinfunction "2_2") (pintype "passive"))
      (node (ref "C91") (pin "2") (pinfunction "2_2") (pintype "passive"))
      (node (ref "C92") (pin "2") (pinfunction "2_2") (pintype "passive"))
      (node (ref "C93") (pin "2") (pinfunction "2_2") (pintype "passive"))
      (node (ref "C94") (pin "2") (pinfunction "2_2") (pintype "passive"))
      (node (ref "C95") (pin "2") (pinfunction "2_2") (pintype "passive"))
      (node (ref "C96") (pin "2") (pinfunction "2_2") (pintype "passive"))
      (node (ref "C97") (pin "2") (pinfunction "2_2") (pintype "passive"))
      (node (ref "C99") (pin "2") (pinfunction "2_2") (pintype "passive"))
      (node (ref "JP1") (pin "5") (pinfunction "5_5") (pintype "passive"))
      (node (ref "LED2") (pin "C") (pinfunction "C_C") (pintype "passive"))
      (node (ref "LED3") (pin "C") (pinfunction "C_C") (pintype "passive"))
      (node (ref "PWR1") (pin "-") (pinfunction "-_-") (pintype "passive"))
      (node (ref "PWR1") (pin "--") (pinfunction "--_--") (pintype "passive"))
      (node (ref "R1") (pin "2") (pinfunction "2_2") (pintype "passive"))
      (node (ref "R12") (pin "1") (pinfunction "1_1") (pintype "passive"))
      (node (ref "R15") (pin "1") (pinfunction "1_1") (pintype "passive"))
      (node (ref "R16") (pin "1") (pinfunction "1_1") (pintype "passive"))
      (node (ref "R24") (pin "1") (pinfunction "1_1") (pintype "passive"))
      (node (ref "R25") (pin "1") (pinfunction "1_1") (pintype "passive"))
      (node (ref "R26") (pin "1") (pinfunction "1_1") (pintype "passive"))
      (node (ref "R27") (pin "1") (pinfunction "1_1") (pintype "passive"))
      (node (ref "R36") (pin "1") (pinfunction "1_1") (pintype "passive"))
      (node (ref "R38") (pin "1") (pinfunction "1_1") (pintype "passive"))
      (node (ref "R4") (pin "1") (pinfunction "1_1") (pintype "passive"))
      (node (ref "R42") (pin "1") (pinfunction "1_1") (pintype "passive"))
      (node (ref "R43") (pin "1") (pinfunction "1_1") (pintype "passive"))
      (node (ref "R5") (pin "1") (pinfunction "1_1") (pintype "passive"))
      (node (ref "R50") (pin "2") (pinfunction "2_2") (pintype "passive"))
      (node (ref "R51") (pin "2") (pinfunction "2_2") (pintype "passive"))
      (node (ref "R6") (pin "1") (pinfunction "1_1") (pintype "passive"))
      (node (ref "R7") (pin "1") (pinfunction "1_1") (pintype "passive"))
      (node (ref "RJ1") (pin "GND") (pinfunction "GND_GND") (pintype "bidirectional"))
      (node (ref "RJ1") (pin "SHIELD0") (pinfunction "SHIELD0_SHIELD0") (pintype "bidirectional"))
      (node (ref "RJ1") (pin "SHIELD1") (pinfunction "SHIELD1_SHIELD1") (pintype "bidirectional"))
      (node (ref "RJ2") (pin "GND") (pinfunction "GND_GND") (pintype "bidirectional"))
      (node (ref "RJ2") (pin "SHIELD0") (pinfunction "SHIELD0_SHIELD0") (pintype "bidirectional"))
      (node (ref "RJ2") (pin "SHIELD1") (pinfunction "SHIELD1_SHIELD1") (pintype "bidirectional"))
      (node (ref "SD") (pin "6") (pinfunction "VSS_6") (pintype "bidirectional"))
      (node (ref "SD") (pin "G1") (pinfunction "GND_G1") (pintype "bidirectional"))
      (node (ref "SD") (pin "G2") (pinfunction "GND_G2") (pintype "bidirectional"))
      (node (ref "SD") (pin "G3") (pinfunction "GND_G3") (pintype "bidirectional"))
      (node (ref "SD") (pin "G4") (pinfunction "GND_G4") (pintype "bidirectional"))
      (node (ref "T1") (pin "2") (pinfunction "E_2") (pintype "passive"))
      (node (ref "T2") (pin "1") (pinfunction "B_1") (pintype "passive"))
      (node (ref "T2") (pin "2") (pinfunction "E_2") (pintype "passive"))
      (node (ref "U1") (pin "105") (pinfunction "VSSA4_105") (pintype "power_in"))
      (node (ref "U1") (pin "112") (pinfunction "VSSA1_112") (pintype "power_in"))
      (node (ref "U1") (pin "118") (pinfunction "VSSA2_118") (pintype "power_in"))
      (node (ref "U1") (pin "30") (pinfunction "VSSD1_30") (pintype "power_in"))
      (node (ref "U1") (pin "35") (pinfunction "VSSD2_35") (pintype "power_in"))
      (node (ref "U1") (pin "98") (pinfunction "DCDC_GND_98") (pintype "power_in"))
      (node (ref "U2") (pin "12") (pinfunction "VSSQ2_12") (pintype "power_in"))
      (node (ref "U2") (pin "34") (pinfunction "VSS1_34") (pintype "power_in"))
      (node (ref "U2") (pin "48") (pinfunction "VSS2_48") (pintype "power_in"))
      (node (ref "U2") (pin "52") (pinfunction "VSSQ3_52") (pintype "power_in"))
      (node (ref "U2") (pin "58") (pinfunction "VSSQ4_58") (pintype "power_in"))
      (node (ref "U2") (pin "6") (pinfunction "VSSQ1_6") (pintype "power_in"))
      (node (ref "U2") (pin "64") (pinfunction "VSSQ5_64") (pintype "power_in"))
      (node (ref "U2") (pin "66") (pinfunction "VSS3_66") (pintype "power_in"))
      (node (ref "U3") (pin "13") (pinfunction "VSS_13") (pintype "power_in"))
      (node (ref "U3") (pin "36") (pinfunction "VSS_36") (pintype "power_in"))
      (node (ref "U4") (pin "34") (pinfunction "TEST2_34") (pintype "passive"))
      (node (ref "U4") (pin "44") (pinfunction "CLK24_EN_44") (pintype "passive"))
      (node (ref "U4") (pin "65") (pinfunction "EPAD_65") (pintype "passive"))
      (node (ref "U5") (pin "13") (pinfunction "TEST2_13") (pintype "power_in"))
      (node (ref "U5") (pin "33") (pinfunction "TEST3_33") (pintype "power_in"))
      (node (ref "U6") (pin "6") (pinfunction "GND_6") (pintype "power_in"))
      (node (ref "U7") (pin "4") (pinfunction "GND_4") (pintype "passive"))
      (node (ref "X1") (pin "4") (pinfunction "4_4") (pintype "passive"))
      (node (ref "X1") (pin "S1") (pinfunction "S1_S1") (pintype "passive"))
      (node (ref "X1") (pin "S2") (pinfunction "S2_S2") (pintype "passive"))
    )
    (net (code "122") (name "Net-(LED1-PadA)") (class "Default")
      (node (ref "LED1") (pin "A") (pinfunction "A_A") (pintype "passive"))
      (node (ref "R33") (pin "2") (pinfunction "2_2") (pintype "passive"))
    )
    (net (code "123") (name "Net-(LED2-PadA)") (class "Default")
      (node (ref "LED2") (pin "A") (pinfunction "A_A") (pintype "passive"))
      (node (ref "R40") (pin "1") (pinfunction "1_1") (pintype "passive"))
    )
    (net (code "124") (name "Net-(LED3-PadA)") (class "Default")
      (node (ref "LED3") (pin "A") (pinfunction "A_A") (pintype "passive"))
      (node (ref "R41") (pin "1") (pinfunction "1_1") (pintype "passive"))
    )
    (net (code "125") (name "Net-(LED4-PadA)") (class "Default")
      (node (ref "LED4") (pin "A") (pinfunction "A_A") (pintype "passive"))
      (node (ref "R49") (pin "2") (pinfunction "2_2") (pintype "passive"))
    )
    (net (code "126") (name "Net-(R5-Pad2)") (class "Default")
      (node (ref "R5") (pin "2") (pinfunction "2_2") (pintype "passive"))
      (node (ref "RJ1") (pin "G-") (pinfunction "G-_G-") (pintype "bidirectional"))
    )
    (net (code "127") (name "Net-(R6-Pad2)") (class "Default")
      (node (ref "R6") (pin "2") (pinfunction "2_2") (pintype "passive"))
      (node (ref "RJ1") (pin "Y-") (pinfunction "Y-_Y-") (pintype "bidirectional"))
    )
    (net (code "128") (name "Net-(R20-Pad1)") (class "Default")
      (node (ref "R20") (pin "1") (pinfunction "1_1") (pintype "passive"))
      (node (ref "SW1") (pin "1") (pinfunction "1_1") (pintype "passive"))
    )
    (net (code "129") (name "Net-(R21-Pad1)") (class "Default")
      (node (ref "R21") (pin "1") (pinfunction "1_1") (pintype "passive"))
      (node (ref "SW1") (pin "2") (pinfunction "2_2") (pintype "passive"))
    )
    (net (code "130") (name "Net-(R22-Pad1)") (class "Default")
      (node (ref "R22") (pin "1") (pinfunction "1_1") (pintype "passive"))
      (node (ref "SW1") (pin "3") (pinfunction "3_3") (pintype "passive"))
    )
    (net (code "131") (name "Net-(R23-Pad1)") (class "Default")
      (node (ref "R23") (pin "1") (pinfunction "1_1") (pintype "passive"))
      (node (ref "SW1") (pin "4") (pinfunction "4_4") (pintype "passive"))
    )
    (net (code "132") (name "Net-(R42-Pad2)") (class "Default")
      (node (ref "R42") (pin "2") (pinfunction "2_2") (pintype "passive"))
      (node (ref "RJ2") (pin "G-") (pinfunction "G-_G-") (pintype "bidirectional"))
    )
    (net (code "133") (name "Net-(R43-Pad2)") (class "Default")
      (node (ref "R43") (pin "2") (pinfunction "2_2") (pintype "passive"))
      (node (ref "RJ2") (pin "Y-") (pinfunction "Y-_Y-") (pintype "bidirectional"))
    )
    (net (code "134") (name "Net-(RJ1-RXCT)") (class "Default")
      (node (ref "C73") (pin "1") (pinfunction "1_1") (pintype "passive"))
      (node (ref "R28") (pin "2") (pinfunction "2_2") (pintype "passive"))
      (node (ref "RJ1") (pin "P4") (pinfunction "TXCT_P4") (pintype "bidirectional"))
      (node (ref "RJ1") (pin "P5") (pinfunction "RXCT_P5") (pintype "bidirectional"))
    )
    (net (code "135") (name "Net-(RJ2-RXCT)") (class "Default")
      (node (ref "C82") (pin "1") (pinfunction "1_1") (pintype "passive"))
      (node (ref "R44") (pin "2") (pinfunction "2_2") (pintype "passive"))
      (node (ref "RJ2") (pin "P4") (pinfunction "TXCT_P4") (pintype "bidirectional"))
      (node (ref "RJ2") (pin "P5") (pinfunction "RXCT_P5") (pintype "bidirectional"))
    )
    (net (code "136") (name "Net-(S1-S)") (class "Default")
      (node (ref "R1") (pin "1") (pinfunction "1_1") (pintype "passive"))
      (node (ref "R2") (pin "1") (pinfunction "1_1") (pintype "passive"))
      (node (ref "S1") (pin "1") (pinfunction "S_1") (pintype "passive"))
      (node (ref "S1") (pin "2") (pinfunction "S1_2") (pintype "passive"))
    )
    (net (code "137") (name "Net-(S2-S)") (class "Default")
      (node (ref "R3") (pin "1") (pinfunction "1_1") (pintype "passive"))
      (node (ref "S2") (pin "1") (pinfunction "S_1") (pintype "passive"))
      (node (ref "S2") (pin "2") (pinfunction "S1_2") (pintype "passive"))
    )
    (net (code "138") (name "Net-(SD-VDD)") (class "Default")
      (node (ref "C40") (pin "2") (pinfunction "2_2") (pintype "passive"))
      (node (ref "C41") (pin "2") (pinfunction "2_2") (pintype "passive"))
      (node (ref "L3") (pin "2") (pinfunction "2_2") (pintype "passive"))
      (node (ref "SD") (pin "4") (pinfunction "VDD_4") (pintype "bidirectional"))
    )
    (net (code "139") (name "Net-(T1-B)") (class "Default")
      (node (ref "C6") (pin "1") (pinfunction "1_1") (pintype "passive"))
      (node (ref "R3") (pin "2") (pinfunction "2_2") (pintype "passive"))
      (node (ref "R4") (pin "2") (pinfunction "2_2") (pintype "passive"))
      (node (ref "T1") (pin "1") (pinfunction "B_1") (pintype "passive"))
    )
    (net (code "140") (name "Net-(U1-DCDC_LN1)") (class "Default")
      (node (ref "L2") (pin "2") (pinfunction "2_2") (pintype "passive"))
      (node (ref "U1") (pin "97") (pinfunction "DCDC_LN1_97") (pintype "passive"))
    )
    (net (code "141") (name "Net-(U1-DCDC_LP)") (class "Default")
      (node (ref "L2") (pin "1") (pinfunction "1_1") (pintype "passive"))
      (node (ref "U1") (pin "99") (pinfunction "DCDC_LP_99") (pintype "passive"))
    )
    (net (code "142") (name "Net-(U1-LCD_RS)") (class "Default")
      (node (ref "R19") (pin "1") (pinfunction "1_1") (pintype "passive"))
      (node (ref "U1") (pin "14") (pinfunction "LCD_RS_14") (pintype "bidirectional"))
    )
    (net (code "143") (name "Net-(U1-VAG)") (class "Default")
      (node (ref "C39") (pin "2") (pinfunction "2_2") (pintype "passive"))
      (node (ref "U1") (pin "117") (pinfunction "VAG_117") (pintype "passive"))
    )
    (net (code "144") (name "Net-(U2-VREF)") (class "Default")
      (node (ref "C52") (pin "1") (pinfunction "1_1") (pintype "passive"))
      (node (ref "C53") (pin "2") (pinfunction "2_2") (pintype "passive"))
      (node (ref "R16") (pin "2") (pinfunction "2_2") (pintype "passive"))
      (node (ref "R17") (pin "1") (pinfunction "1_1") (pintype "passive"))
      (node (ref "U2") (pin "49") (pinfunction "VREF_49") (pintype "input"))
    )
    (net (code "145") (name "Net-(U4-AUTOMDIX_EN)") (class "Default")
      (node (ref "R39") (pin "2") (pinfunction "2_2") (pintype "passive"))
      (node (ref "U4") (pin "41") (pinfunction "AUTOMDIX_EN_41") (pintype "passive"))
    )
    (net (code "146") (name "Net-(U4-EXRES)") (class "Default")
      (node (ref "R38") (pin "2") (pinfunction "2_2") (pintype "passive"))
      (node (ref "U4") (pin "50") (pinfunction "EXRES_50") (pintype "passive"))
    )
    (net (code "147") (name "Net-(U4-NRESET)") (class "Default")
      (node (ref "C76") (pin "1") (pinfunction "1_1") (pintype "passive"))
      (node (ref "R37") (pin "1") (pinfunction "1_1") (pintype "passive"))
      (node (ref "U4") (pin "12") (pinfunction "NRESET_12") (pintype "passive"))
    )
    (net (code "148") (name "Net-(U4-USBRBIAS)") (class "Default")
      (node (ref "R36") (pin "2") (pinfunction "2_2") (pintype "passive"))
      (node (ref "U4") (pin "63") (pinfunction "USBRBIAS_63") (pintype "passive"))
    )
    (net (code "149") (name "Net-(U4-VBUS_DET)") (class "Default")
      (node (ref "R35") (pin "1") (pinfunction "1_1") (pintype "passive"))
      (node (ref "U4") (pin "11") (pinfunction "VBUS_DET_11") (pintype "power_in"))
    )
    (net (code "150") (name "Net-(U4-XI)") (class "Default")
      (node (ref "C75") (pin "1") (pinfunction "1_1") (pintype "passive"))
      (node (ref "Q2") (pin "2") (pinfunction "2_2") (pintype "passive"))
      (node (ref "R34") (pin "2") (pinfunction "2_2") (pintype "passive"))
      (node (ref "U4") (pin "61") (pinfunction "XI_61") (pintype "passive"))
    )
    (net (code "151") (name "Net-(U4-XO)") (class "Default")
      (node (ref "C74") (pin "1") (pinfunction "1_1") (pintype "passive"))
      (node (ref "Q2") (pin "1") (pinfunction "1_1") (pintype "passive"))
      (node (ref "R34") (pin "1") (pinfunction "1_1") (pintype "passive"))
      (node (ref "U4") (pin "60") (pinfunction "XO_60") (pintype "passive"))
    )
    (net (code "152") (name "Net-(U5A-EXRES)") (class "Default")
      (node (ref "R50") (pin "1") (pinfunction "1_1") (pintype "passive"))
      (node (ref "U5") (pin "8") (pinfunction "EXRES_8") (pintype "input"))
    )
    (net (code "153") (name "Net-(U5A-USBRBIAS)") (class "Default")
      (node (ref "R51") (pin "1") (pinfunction "1_1") (pintype "passive"))
      (node (ref "U5") (pin "16") (pinfunction "USBRBIAS_16") (pintype "input"))
    )
    (net (code "154") (name "Net-(U5A-VBUS_DET)") (class "Default")
      (node (ref "R52") (pin "1") (pinfunction "1_1") (pintype "passive"))
      (node (ref "U5") (pin "20") (pinfunction "VBUS_DET_20") (pintype "power_in"))
    )
    (net (code "155") (name "Net-(U5A-VDDUSBPLL)") (class "Default")
      (node (ref "L5") (pin "2") (pinfunction "2_2") (pintype "passive"))
      (node (ref "U5") (pin "17") (pinfunction "VDDUSBPLL_17") (pintype "power_in"))
    )
    (net (code "156") (name "Net-(U5A-XO)") (class "Default")
      (node (ref "C85") (pin "1") (pinfunction "1_1") (pintype "passive"))
      (node (ref "Q3") (pin "2") (pinfunction "2_2") (pintype "passive"))
      (node (ref "U5") (pin "19") (pinfunction "XO_19") (pintype "output"))
    )
    (net (code "157") (name "Net-(U7-VI)") (class "Default")
      (node (ref "C1") (pin "1") (pinfunction "1_1") (pintype "passive"))
      (node (ref "PWR1") (pin "+") (pinfunction "+_+") (pintype "passive"))
      (node (ref "U7") (pin "1") (pinfunction "VI_1") (pintype "input"))
    )
    (net (code "158") (name "unconnected-(RJ1-PadNC)") (class "Default")
      (node (ref "RJ1") (pin "NC") (pinfunction "NC_NC") (pintype "bidirectional"))
    )
    (net (code "159") (name "unconnected-(RJ2-PadNC)") (class "Default")
      (node (ref "RJ2") (pin "NC") (pinfunction "NC_NC") (pintype "bidirectional"))
    )
    (net (code "160") (name "unconnected-(U1-GPMI_CE1N-Pad81)") (class "Default")
      (node (ref "U1") (pin "81") (pinfunction "GPMI_CE1N_81") (pintype "bidirectional"))
    )
    (net (code "161") (name "unconnected-(U1-GPMI_RDY1{slash}SSP2_CMD-Pad21)") (class "Default")
      (node (ref "U1") (pin "21") (pinfunction "GPMI_RDY1/SSP2_CMD_21") (pintype "bidirectional"))
    )
    (net (code "162") (name "unconnected-(U1-HPL-Pad113)") (class "Default")
      (node (ref "U1") (pin "113") (pinfunction "HPL_113") (pintype "output"))
    )
    (net (code "163") (name "unconnected-(U1-HPR-Pad109)") (class "Default")
      (node (ref "U1") (pin "109") (pinfunction "HPR_109") (pintype "output"))
    )
    (net (code "164") (name "unconnected-(U1-LCD_CS-Pad10)") (class "Default")
      (node (ref "U1") (pin "10") (pinfunction "LCD_CS_10") (pintype "bidirectional"))
    )
    (net (code "165") (name "unconnected-(U1-LCD_D04-Pad6)") (class "Default")
      (node (ref "U1") (pin "6") (pinfunction "LCD_D04_6") (pintype "bidirectional"))
    )
    (net (code "166") (name "unconnected-(U1-LCD_D05-Pad7)") (class "Default")
      (node (ref "U1") (pin "7") (pinfunction "LCD_D05_7") (pintype "bidirectional"))
    )
    (net (code "167") (name "unconnected-(U1-LCD_D06-Pad8)") (class "Default")
      (node (ref "U1") (pin "8") (pinfunction "LCD_D06_8") (pintype "bidirectional"))
    )
    (net (code "168") (name "unconnected-(U1-LCD_D07-Pad9)") (class "Default")
      (node (ref "U1") (pin "9") (pinfunction "LCD_D07_9") (pintype "bidirectional"))
    )
    (net (code "169") (name "unconnected-(U1-LCD_DOTCK{slash}GPMI_RDY3-Pad17)") (class "Default")
      (node (ref "U1") (pin "17") (pinfunction "LCD_DOTCK/GPMI_RDY3_17") (pintype "bidirectional"))
    )
    (net (code "170") (name "unconnected-(U1-LCD_RESET{slash}GPMI_CE3N-Pad12)") (class "Default")
      (node (ref "U1") (pin "12") (pinfunction "LCD_RESET/GPMI_CE3N_12") (pintype "bidirectional"))
    )
    (net (code "171") (name "unconnected-(U1-LCD_VSYNC{slash}LCD_BUSY-Pad16)") (class "Default")
      (node (ref "U1") (pin "16") (pinfunction "LCD_VSYNC/LCD_BUSY_16") (pintype "bidirectional"))
    )
    (net (code "172") (name "unconnected-(U1-LCD_WR-Pad13)") (class "Default")
      (node (ref "U1") (pin "13") (pinfunction "LCD_WR_13") (pintype "bidirectional"))
    )
    (net (code "173") (name "unconnected-(U1-LINE1_INL-Pad115)") (class "Default")
      (node (ref "U1") (pin "115") (pinfunction "LINE1_INL_115") (pintype "input"))
    )
    (net (code "174") (name "unconnected-(U1-LINE1_INR-Pad114)") (class "Default")
      (node (ref "U1") (pin "114") (pinfunction "LINE1_INR_114") (pintype "input"))
    )
    (net (code "175") (name "unconnected-(U1-LRADC0-Pad108)") (class "Default")
      (node (ref "U1") (pin "108") (pinfunction "LRADC0_108") (pintype "bidirectional"))
    )
    (net (code "176") (name "unconnected-(U1-LRADC1-Pad107)") (class "Default")
      (node (ref "U1") (pin "107") (pinfunction "LRADC1_107") (pintype "bidirectional"))
    )
    (net (code "177") (name "unconnected-(U1-MIC-Pad116)") (class "Default")
      (node (ref "U1") (pin "116") (pinfunction "MIC_116") (pintype "input"))
    )
    (net (code "178") (name "unconnected-(U1-PWM2{slash}GPMI_RDY3-Pad91)") (class "Default")
      (node (ref "U1") (pin "91") (pinfunction "PWM2/GPMI_RDY3_91") (pintype "bidirectional"))
    )
    (net (code "179") (name "unconnected-(U1-SSP1_DETECT{slash}GPMI_CE3N{slash}USB_ID-Pad88)") (class "Default")
      (node (ref "U1") (pin "88") (pinfunction "SSP1_DETECT/GPMI_CE3N/USB_ID_88") (pintype "bidirectional"))
    )
    (net (code "180") (name "unconnected-(U1-VDAC1-Pad104)") (class "Default")
      (node (ref "U1") (pin "104") (pinfunction "VDAC1_104") (pintype "output"))
    )
    (net (code "181") (name "unconnected-(U2-NC1-Pad14)") (class "Default")
      (node (ref "U2") (pin "14") (pinfunction "NC1_14") (pintype "no_connect"))
    )
    (net (code "182") (name "unconnected-(U2-NC2-Pad17)") (class "Default")
      (node (ref "U2") (pin "17") (pinfunction "NC2_17") (pintype "no_connect"))
    )
    (net (code "183") (name "unconnected-(U2-NC3-Pad19)") (class "Default")
      (node (ref "U2") (pin "19") (pinfunction "NC3_19") (pintype "no_connect"))
    )
    (net (code "184") (name "unconnected-(U2-NC4-Pad25)") (class "Default")
      (node (ref "U2") (pin "25") (pinfunction "NC4_25") (pintype "no_connect"))
    )
    (net (code "185") (name "unconnected-(U2-NC5-Pad43)") (class "Default")
      (node (ref "U2") (pin "43") (pinfunction "NC5_43") (pintype "no_connect"))
    )
    (net (code "186") (name "unconnected-(U2-NC6-Pad50)") (class "Default")
      (node (ref "U2") (pin "50") (pinfunction "NC6_50") (pintype "no_connect"))
    )
    (net (code "187") (name "unconnected-(U2-NC7-Pad53)") (class "Default")
      (node (ref "U2") (pin "53") (pinfunction "NC7_53") (pintype "no_connect"))
    )
    (net (code "188") (name "unconnected-(U3-NC-Pad1)") (class "Default")
      (node (ref "U3") (pin "1") (pinfunction "NC_1") (pintype "no_connect"))
    )
    (net (code "189") (name "unconnected-(U3-NC-Pad2)") (class "Default")
      (node (ref "U3") (pin "2") (pinfunction "NC_2") (pintype "no_connect"))
    )
    (net (code "190") (name "unconnected-(U3-NC-Pad3)") (class "Default")
      (node (ref "U3") (pin "3") (pinfunction "NC_3") (pintype "no_connect"))
    )
    (net (code "191") (name "unconnected-(U3-NC-Pad4)") (class "Default")
      (node (ref "U3") (pin "4") (pinfunction "NC_4") (pintype "no_connect"))
    )
    (net (code "192") (name "unconnected-(U3-NC-Pad5)") (class "Default")
      (node (ref "U3") (pin "5") (pinfunction "NC_5") (pintype "no_connect"))
    )
    (net (code "193") (name "unconnected-(U3-NC-Pad6)") (class "Default")
      (node (ref "U3") (pin "6") (pinfunction "NC_6") (pintype "no_connect"))
    )
    (net (code "194") (name "unconnected-(U3-NC-Pad10)") (class "Default")
      (node (ref "U3") (pin "10") (pinfunction "NC_10") (pintype "no_connect"))
    )
    (net (code "195") (name "unconnected-(U3-NC-Pad11)") (class "Default")
      (node (ref "U3") (pin "11") (pinfunction "NC_11") (pintype "no_connect"))
    )
    (net (code "196") (name "unconnected-(U3-NC-Pad14)") (class "Default")
      (node (ref "U3") (pin "14") (pinfunction "NC_14") (pintype "no_connect"))
    )
    (net (code "197") (name "unconnected-(U3-NC-Pad15)") (class "Default")
      (node (ref "U3") (pin "15") (pinfunction "NC_15") (pintype "no_connect"))
    )
    (net (code "198") (name "unconnected-(U3-NC-Pad20)") (class "Default")
      (node (ref "U3") (pin "20") (pinfunction "NC_20") (pintype "no_connect"))
    )
    (net (code "199") (name "unconnected-(U3-NC-Pad21)") (class "Default")
      (node (ref "U3") (pin "21") (pinfunction "NC_21") (pintype "no_connect"))
    )
    (net (code "200") (name "unconnected-(U3-NC-Pad22)") (class "Default")
      (node (ref "U3") (pin "22") (pinfunction "NC_22") (pintype "no_connect"))
    )
    (net (code "201") (name "unconnected-(U3-NC-Pad23)") (class "Default")
      (node (ref "U3") (pin "23") (pinfunction "NC_23") (pintype "no_connect"))
    )
    (net (code "202") (name "unconnected-(U3-NC-Pad24)") (class "Default")
      (node (ref "U3") (pin "24") (pinfunction "NC_24") (pintype "no_connect"))
    )
    (net (code "203") (name "unconnected-(U3-NC-Pad25)") (class "Default")
      (node (ref "U3") (pin "25") (pinfunction "NC_25") (pintype "no_connect"))
    )
    (net (code "204") (name "unconnected-(U3-NC-Pad26)") (class "Default")
      (node (ref "U3") (pin "26") (pinfunction "NC_26") (pintype "no_connect"))
    )
    (net (code "205") (name "unconnected-(U3-NC-Pad27)") (class "Default")
      (node (ref "U3") (pin "27") (pinfunction "NC_27") (pintype "no_connect"))
    )
    (net (code "206") (name "unconnected-(U3-NC-Pad28)") (class "Default")
      (node (ref "U3") (pin "28") (pinfunction "NC_28") (pintype "no_connect"))
    )
    (net (code "207") (name "unconnected-(U3-NC-Pad33)") (class "Default")
      (node (ref "U3") (pin "33") (pinfunction "NC_33") (pintype "no_connect"))
    )
    (net (code "208") (name "unconnected-(U3-NC-Pad34)") (class "Default")
      (node (ref "U3") (pin "34") (pinfunction "NC_34") (pintype "no_connect"))
    )
    (net (code "209") (name "unconnected-(U3-NC-Pad35)") (class "Default")
      (node (ref "U3") (pin "35") (pinfunction "NC_35") (pintype "no_connect"))
    )
    (net (code "210") (name "unconnected-(U3-NC-Pad38)") (class "Default")
      (node (ref "U3") (pin "38") (pinfunction "NC_38") (pintype "no_connect"))
    )
    (net (code "211") (name "unconnected-(U3-NC-Pad39)") (class "Default")
      (node (ref "U3") (pin "39") (pinfunction "NC_39") (pintype "no_connect"))
    )
    (net (code "212") (name "unconnected-(U3-NC-Pad40)") (class "Default")
      (node (ref "U3") (pin "40") (pinfunction "NC_40") (pintype "no_connect"))
    )
    (net (code "213") (name "unconnected-(U3-NC-Pad45)") (class "Default")
      (node (ref "U3") (pin "45") (pinfunction "NC_45") (pintype "no_connect"))
    )
    (net (code "214") (name "unconnected-(U3-NC-Pad46)") (class "Default")
      (node (ref "U3") (pin "46") (pinfunction "NC_46") (pintype "no_connect"))
    )
    (net (code "215") (name "unconnected-(U3-NC-Pad47)") (class "Default")
      (node (ref "U3") (pin "47") (pinfunction "NC_47") (pintype "no_connect"))
    )
    (net (code "216") (name "unconnected-(U3-NC-Pad48)") (class "Default")
      (node (ref "U3") (pin "48") (pinfunction "NC_48") (pintype "no_connect"))
    )
    (net (code "217") (name "unconnected-(U4-CLK24_OUT-Pad45)") (class "Default")
      (node (ref "U4") (pin "45") (pinfunction "CLK24_OUT_45") (pintype "passive"))
    )
    (net (code "218") (name "unconnected-(U4-EECLK-Pad23)") (class "Default")
      (node (ref "U4") (pin "23") (pinfunction "EECLK_23") (pintype "passive"))
    )
    (net (code "219") (name "unconnected-(U4-EECS-Pad24)") (class "Default")
      (node (ref "U4") (pin "24") (pinfunction "EECS_24") (pintype "passive"))
    )
    (net (code "220") (name "unconnected-(U4-EEDI-Pad26)") (class "Default")
      (node (ref "U4") (pin "26") (pinfunction "EEDI_26") (pintype "passive"))
    )
    (net (code "221") (name "unconnected-(U4-EEDO-Pad25)") (class "Default")
      (node (ref "U4") (pin "25") (pinfunction "EEDO_25") (pintype "passive"))
    )
    (net (code "222") (name "unconnected-(U4-GPIO3-Pad35)") (class "Default")
      (node (ref "U4") (pin "35") (pinfunction "GPIO3_35") (pintype "bidirectional"))
    )
    (net (code "223") (name "unconnected-(U4-GPIO4-Pad36)") (class "Default")
      (node (ref "U4") (pin "36") (pinfunction "GPIO4_36") (pintype "bidirectional"))
    )
    (net (code "224") (name "unconnected-(U4-GPIO5-Pad37)") (class "Default")
      (node (ref "U4") (pin "37") (pinfunction "GPIO5_37") (pintype "bidirectional"))
    )
    (net (code "225") (name "unconnected-(U4-GPIO6-Pad42)") (class "Default")
      (node (ref "U4") (pin "42") (pinfunction "GPIO6_42") (pintype "bidirectional"))
    )
    (net (code "226") (name "unconnected-(U4-GPIO7-Pad43)") (class "Default")
      (node (ref "U4") (pin "43") (pinfunction "GPIO7_43") (pintype "bidirectional"))
    )
    (net (code "227") (name "unconnected-(U4-NC-Pad18)") (class "Default")
      (node (ref "U4") (pin "18") (pinfunction "NC_18") (pintype "no_connect"))
    )
    (net (code "228") (name "unconnected-(U4-NC_2-Pad6)") (class "Default")
      (node (ref "U4") (pin "6") (pinfunction "NC_2_6") (pintype "no_connect"))
    )
    (net (code "229") (name "unconnected-(U4-NC_3-Pad7)") (class "Default")
      (node (ref "U4") (pin "7") (pinfunction "NC_3_7") (pintype "no_connect"))
    )
    (net (code "230") (name "unconnected-(U4-NC_4-Pad8)") (class "Default")
      (node (ref "U4") (pin "8") (pinfunction "NC_4_8") (pintype "no_connect"))
    )
    (net (code "231") (name "unconnected-(U4-NC_5-Pad9)") (class "Default")
      (node (ref "U4") (pin "9") (pinfunction "NC_5_9") (pintype "no_connect"))
    )
    (net (code "232") (name "unconnected-(U4-NC_6-Pad17)") (class "Default")
      (node (ref "U4") (pin "17") (pinfunction "NC_6_17") (pintype "no_connect"))
    )
    (net (code "233") (name "unconnected-(U4-TDO-Pad31)") (class "Default")
      (node (ref "U4") (pin "31") (pinfunction "TDO_31") (pintype "passive"))
    )
    (net (code "234") (name "unconnected-(U4-TEST1-Pad13)") (class "Default")
      (node (ref "U4") (pin "13") (pinfunction "TEST1_13") (pintype "passive"))
    )
    (net (code "235") (name "unconnected-(U4-TEST4-Pad47)") (class "Default")
      (node (ref "U4") (pin "47") (pinfunction "TEST4_47") (pintype "passive"))
    )
    (net (code "236") (name "unconnected-(U5A-EEDI-Pad32)") (class "Default")
      (node (ref "U5") (pin "32") (pinfunction "EEDI_32") (pintype "input"))
    )
    (net (code "237") (name "unconnected-(U5A-EEDO{slash}~{AUTOMDIX_EN}-Pad31)") (class "Default")
      (node (ref "U5") (pin "31") (pinfunction "EEDO/~{AUTOMDIX_EN}_31") (pintype "passive"))
    )
    (net (code "238") (name "unconnected-(U5A-EP-Pad57)") (class "Default")
      (node (ref "U5") (pin "57") (pinfunction "EP_57") (pintype "passive"))
    )
    (net (code "239") (name "unconnected-(U5A-MDC{slash}GPIO2-Pad22)") (class "Default")
      (node (ref "U5") (pin "22") (pinfunction "MDC/GPIO2_22") (pintype "bidirectional"))
    )
    (net (code "240") (name "unconnected-(U5A-MDIO{slash}GPIO1-Pad23)") (class "Default")
      (node (ref "U5") (pin "23") (pinfunction "MDIO/GPIO1_23") (pintype "bidirectional"))
    )
    (net (code "241") (name "unconnected-(U5A-NC-Pad14)") (class "Default")
      (node (ref "U5") (pin "14") (pinfunction "NC_14") (pintype "no_connect"))
    )
    (net (code "242") (name "unconnected-(U5A-NC_2-Pad7)") (class "Default")
      (node (ref "U5") (pin "7") (pinfunction "NC_2_7") (pintype "no_connect"))
    )
    (net (code "243") (name "unconnected-(U5A-NPHY_INT-Pad1)") (class "Default")
      (node (ref "U5") (pin "1") (pinfunction "NPHY_INT_1") (pintype "passive"))
    )
    (net (code "244") (name "unconnected-(U5A-RXCLK-Pad41)") (class "Default")
      (node (ref "U5") (pin "41") (pinfunction "RXCLK_41") (pintype "input"))
    )
    (net (code "245") (name "unconnected-(U5B-COL{slash}GPIO0-Pad46)") (class "Default")
      (node (ref "U5") (pin "46") (pinfunction "COL/GPIO0_46") (pintype "bidirectional"))
    )
    (net (code "246") (name "unconnected-(U5B-CRS{slash}GPIO3-Pad45)") (class "Default")
      (node (ref "U5") (pin "45") (pinfunction "CRS/GPIO3_45") (pintype "bidirectional"))
    )
    (net (code "247") (name "unconnected-(U5B-EECLK{slash}~{PWR_SEL}-Pad29)") (class "Default")
      (node (ref "U5") (pin "29") (pinfunction "EECLK/~{PWR_SEL}_29") (pintype "input"))
    )
    (net (code "248") (name "unconnected-(U5B-EECS-Pad30)") (class "Default")
      (node (ref "U5") (pin "30") (pinfunction "EECS_30") (pintype "input"))
    )
    (net (code "249") (name "unconnected-(U5B-NTRST{slash}RXD0-Pad36)") (class "Default")
      (node (ref "U5") (pin "36") (pinfunction "NTRST/RXD0_36") (pintype "input"))
    )
    (net (code "250") (name "unconnected-(U5B-PHY_SEL-Pad34)") (class "Default")
      (node (ref "U5") (pin "34") (pinfunction "PHY_SEL_34") (pintype "input"))
    )
    (net (code "251") (name "unconnected-(U5B-RXDV-Pad42)") (class "Default")
      (node (ref "U5") (pin "42") (pinfunction "RXDV_42") (pintype "input"))
    )
    (net (code "252") (name "unconnected-(U5B-RXER-Pad44)") (class "Default")
      (node (ref "U5") (pin "44") (pinfunction "RXER_44") (pintype "input"))
    )
    (net (code "253") (name "unconnected-(U5B-TCK{slash}RXD1-Pad38)") (class "Default")
      (node (ref "U5") (pin "38") (pinfunction "TCK/RXD1_38") (pintype "input"))
    )
    (net (code "254") (name "unconnected-(U5B-TDI{slash}RXD3-Pad40)") (class "Default")
      (node (ref "U5") (pin "40") (pinfunction "TDI/RXD3_40") (pintype "input"))
    )
    (net (code "255") (name "unconnected-(U5B-TDO{slash}NPHY_RST-Pad37)") (class "Default")
      (node (ref "U5") (pin "37") (pinfunction "TDO/NPHY_RST_37") (pintype "output"))
    )
    (net (code "256") (name "unconnected-(U5B-TMS{slash}RXD2-Pad39)") (class "Default")
      (node (ref "U5") (pin "39") (pinfunction "TMS/RXD2_39") (pintype "input"))
    )
    (net (code "257") (name "unconnected-(U5B-TXCLK-Pad47)") (class "Default")
      (node (ref "U5") (pin "47") (pinfunction "TXCLK_47") (pintype "input"))
    )
    (net (code "258") (name "unconnected-(U5B-TXD0{slash}GPIO4{slash}~{EEP_DISABLE}-Pad56)") (class "Default")
      (node (ref "U5") (pin "56") (pinfunction "TXD0/GPIO4/~{EEP_DISABLE}_56") (pintype "bidirectional"))
    )
    (net (code "259") (name "unconnected-(U5B-TXD1{slash}GPIO5{slash}~{RMT_WKP}-Pad55)") (class "Default")
      (node (ref "U5") (pin "55") (pinfunction "TXD1/GPIO5/~{RMT_WKP}_55") (pintype "bidirectional"))
    )
    (net (code "260") (name "unconnected-(U5B-TXD2{slash}GPIO6{slash}~{PORT_SWAP}-Pad54)") (class "Default")
      (node (ref "U5") (pin "54") (pinfunction "TXD2/GPIO6/~{PORT_SWAP}_54") (pintype "bidirectional"))
    )
    (net (code "261") (name "unconnected-(U5B-TXD3{slash}GPIO7{slash}~{EEP_SIZE}-Pad53)") (class "Default")
      (node (ref "U5") (pin "53") (pinfunction "TXD3/GPIO7/~{EEP_SIZE}_53") (pintype "bidirectional"))
    )
    (net (code "262") (name "unconnected-(U5B-TXEN-Pad43)") (class "Default")
      (node (ref "U5") (pin "43") (pinfunction "TXEN_43") (pintype "output"))
    )
  )
)
